# N2onboardTelemetry.net
KiCad netlist of a schematic drawn in EasyEDA
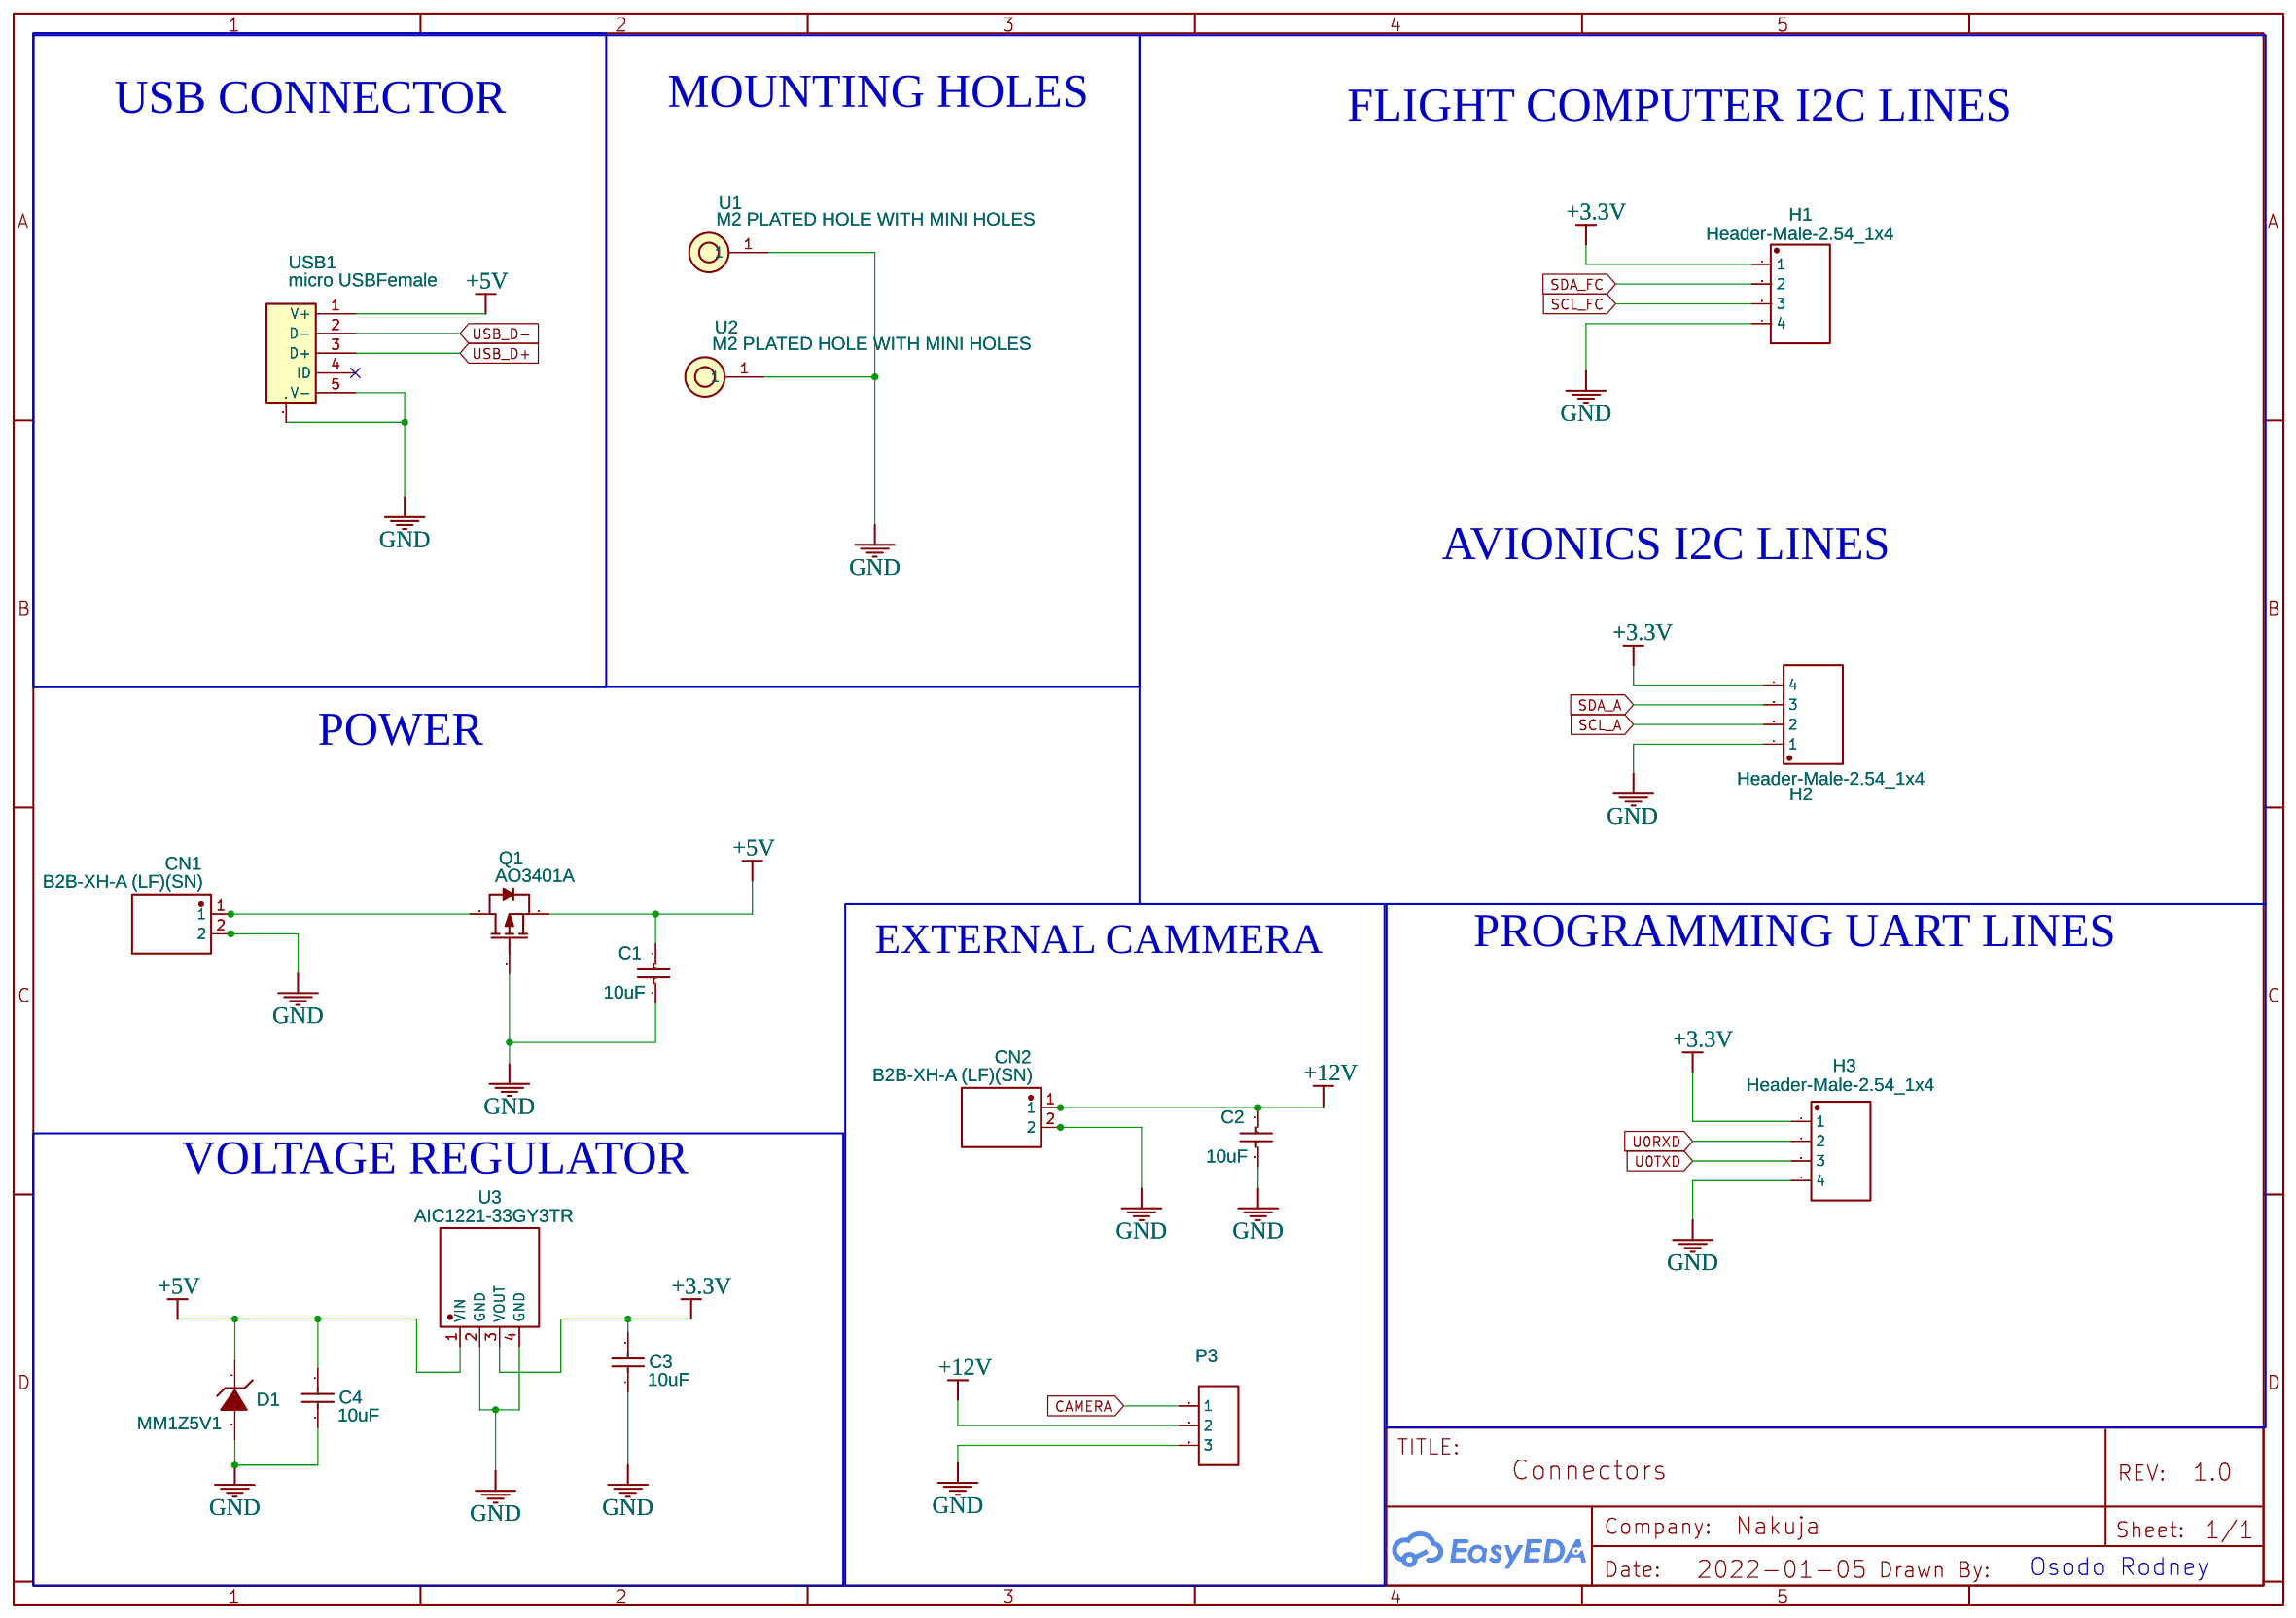
[diagram p0: Connectors]
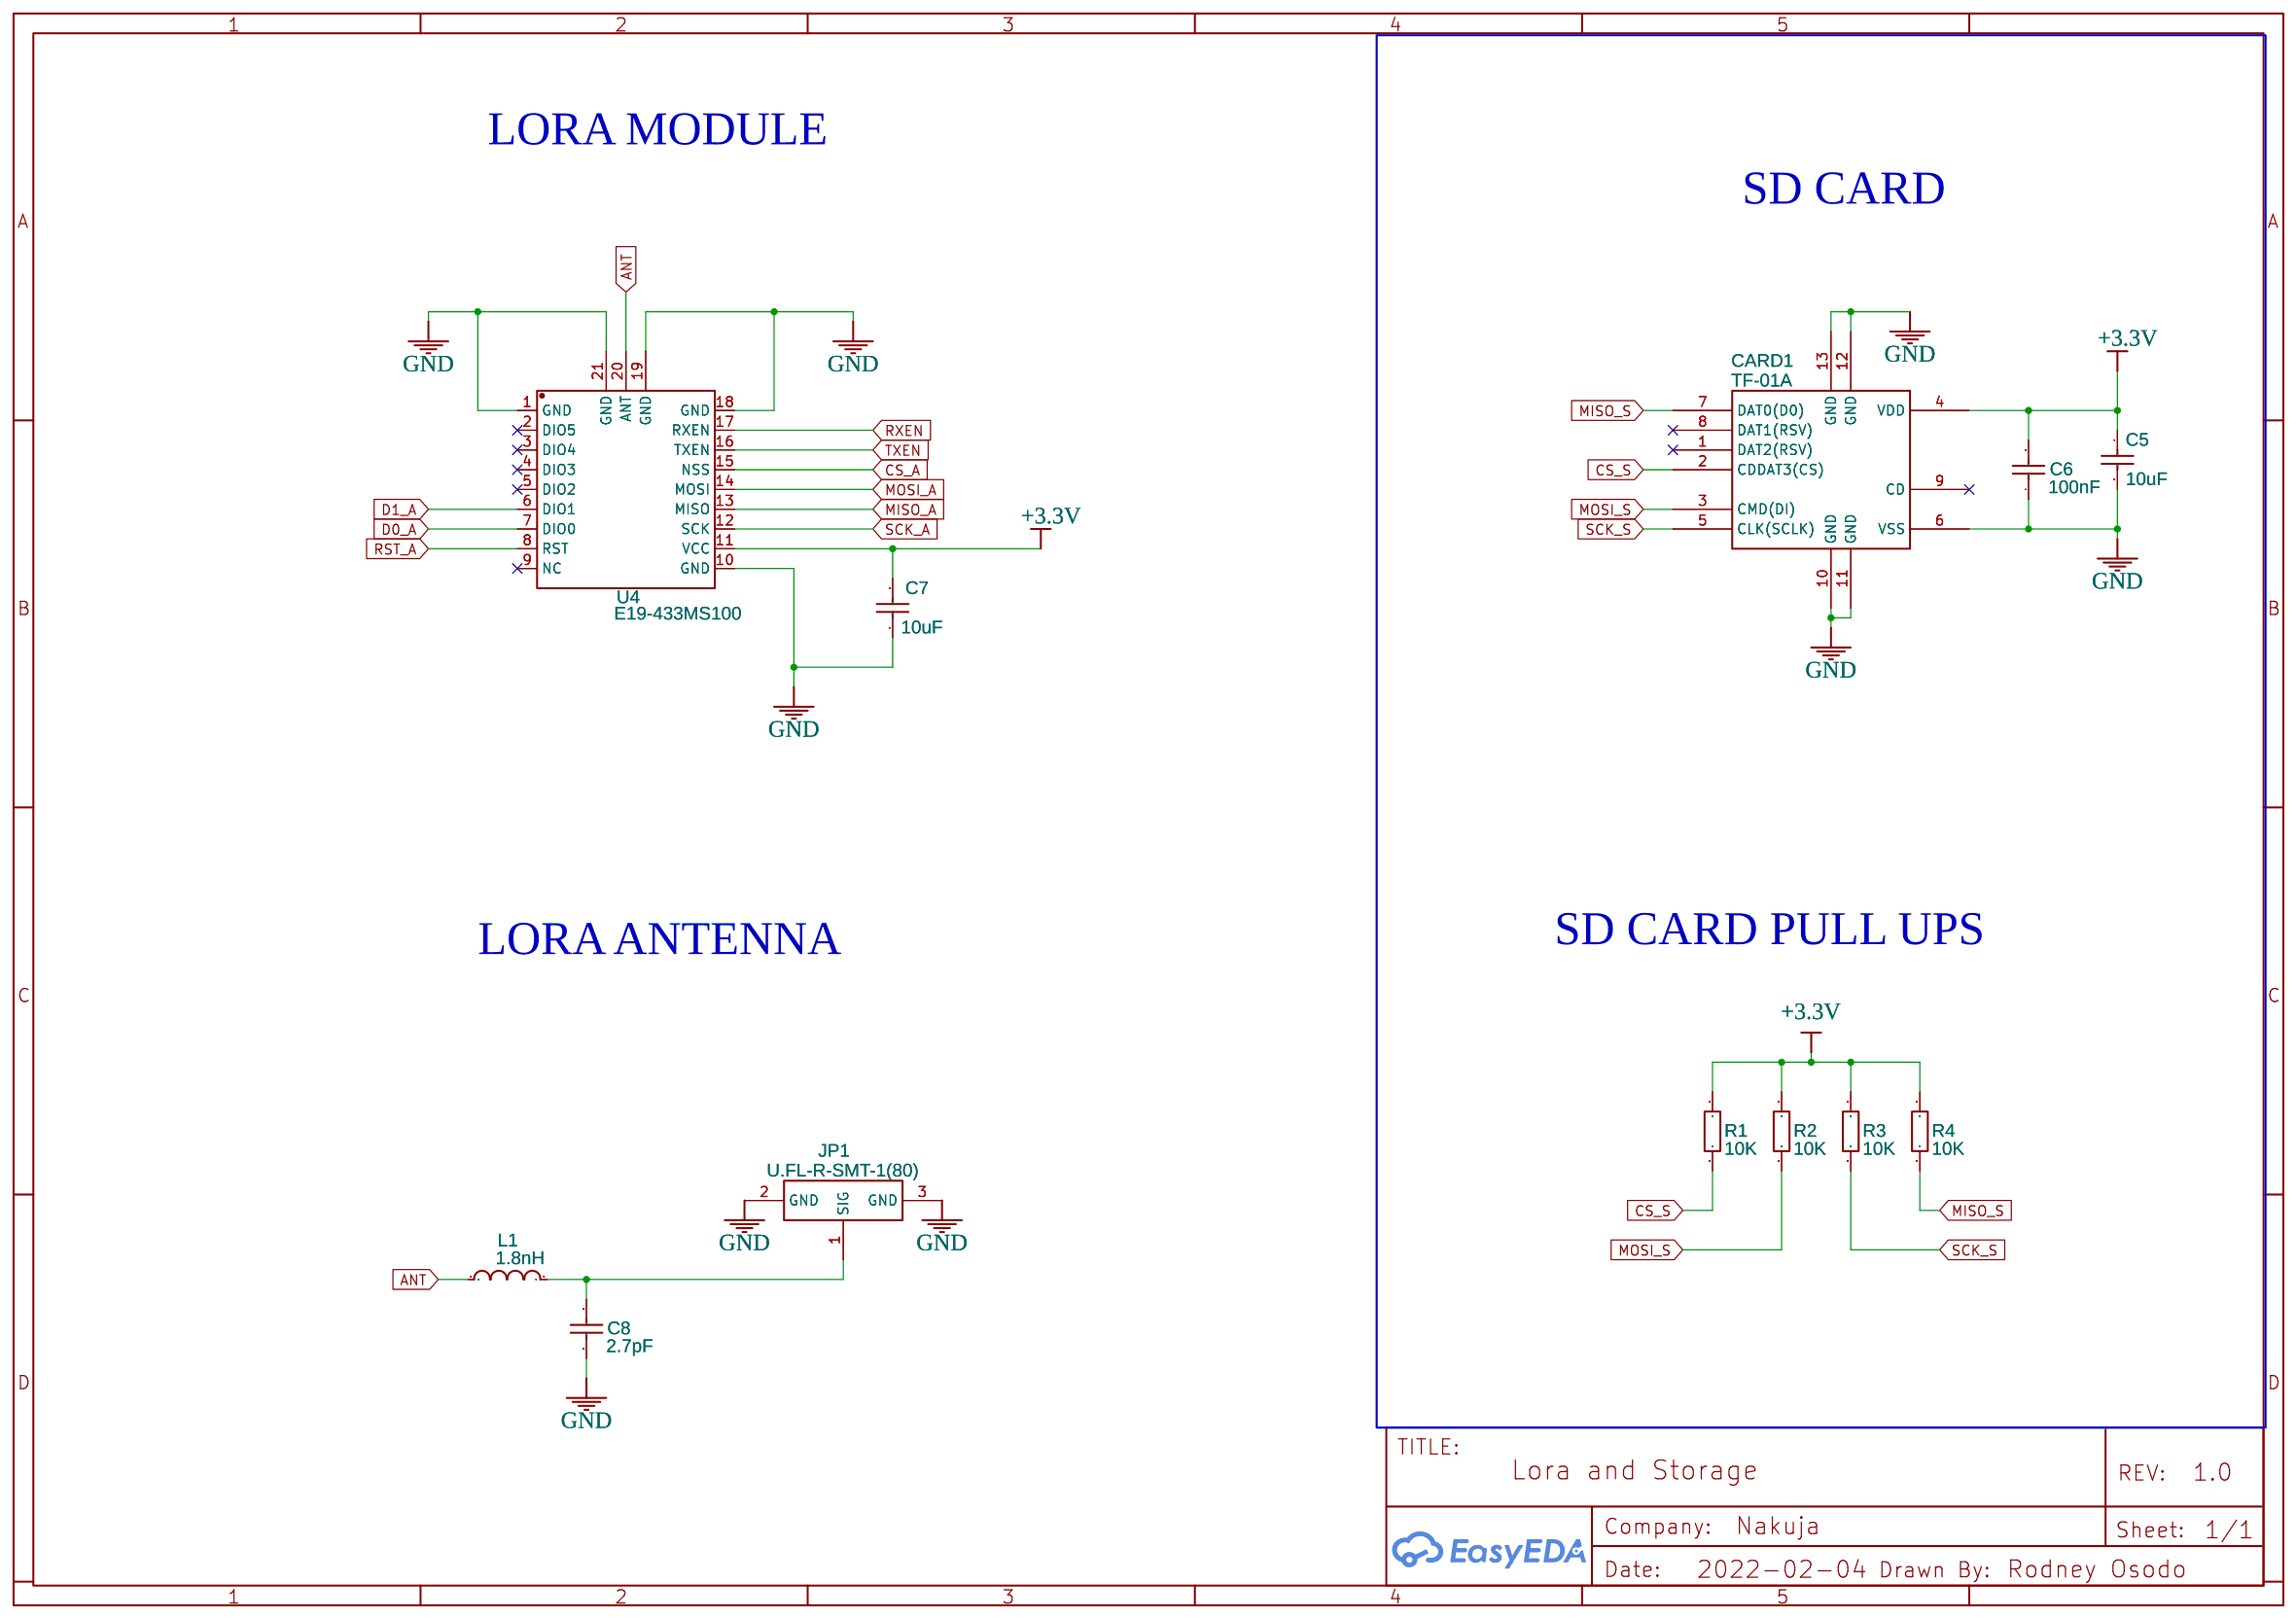
[diagram p1: lora&storage]
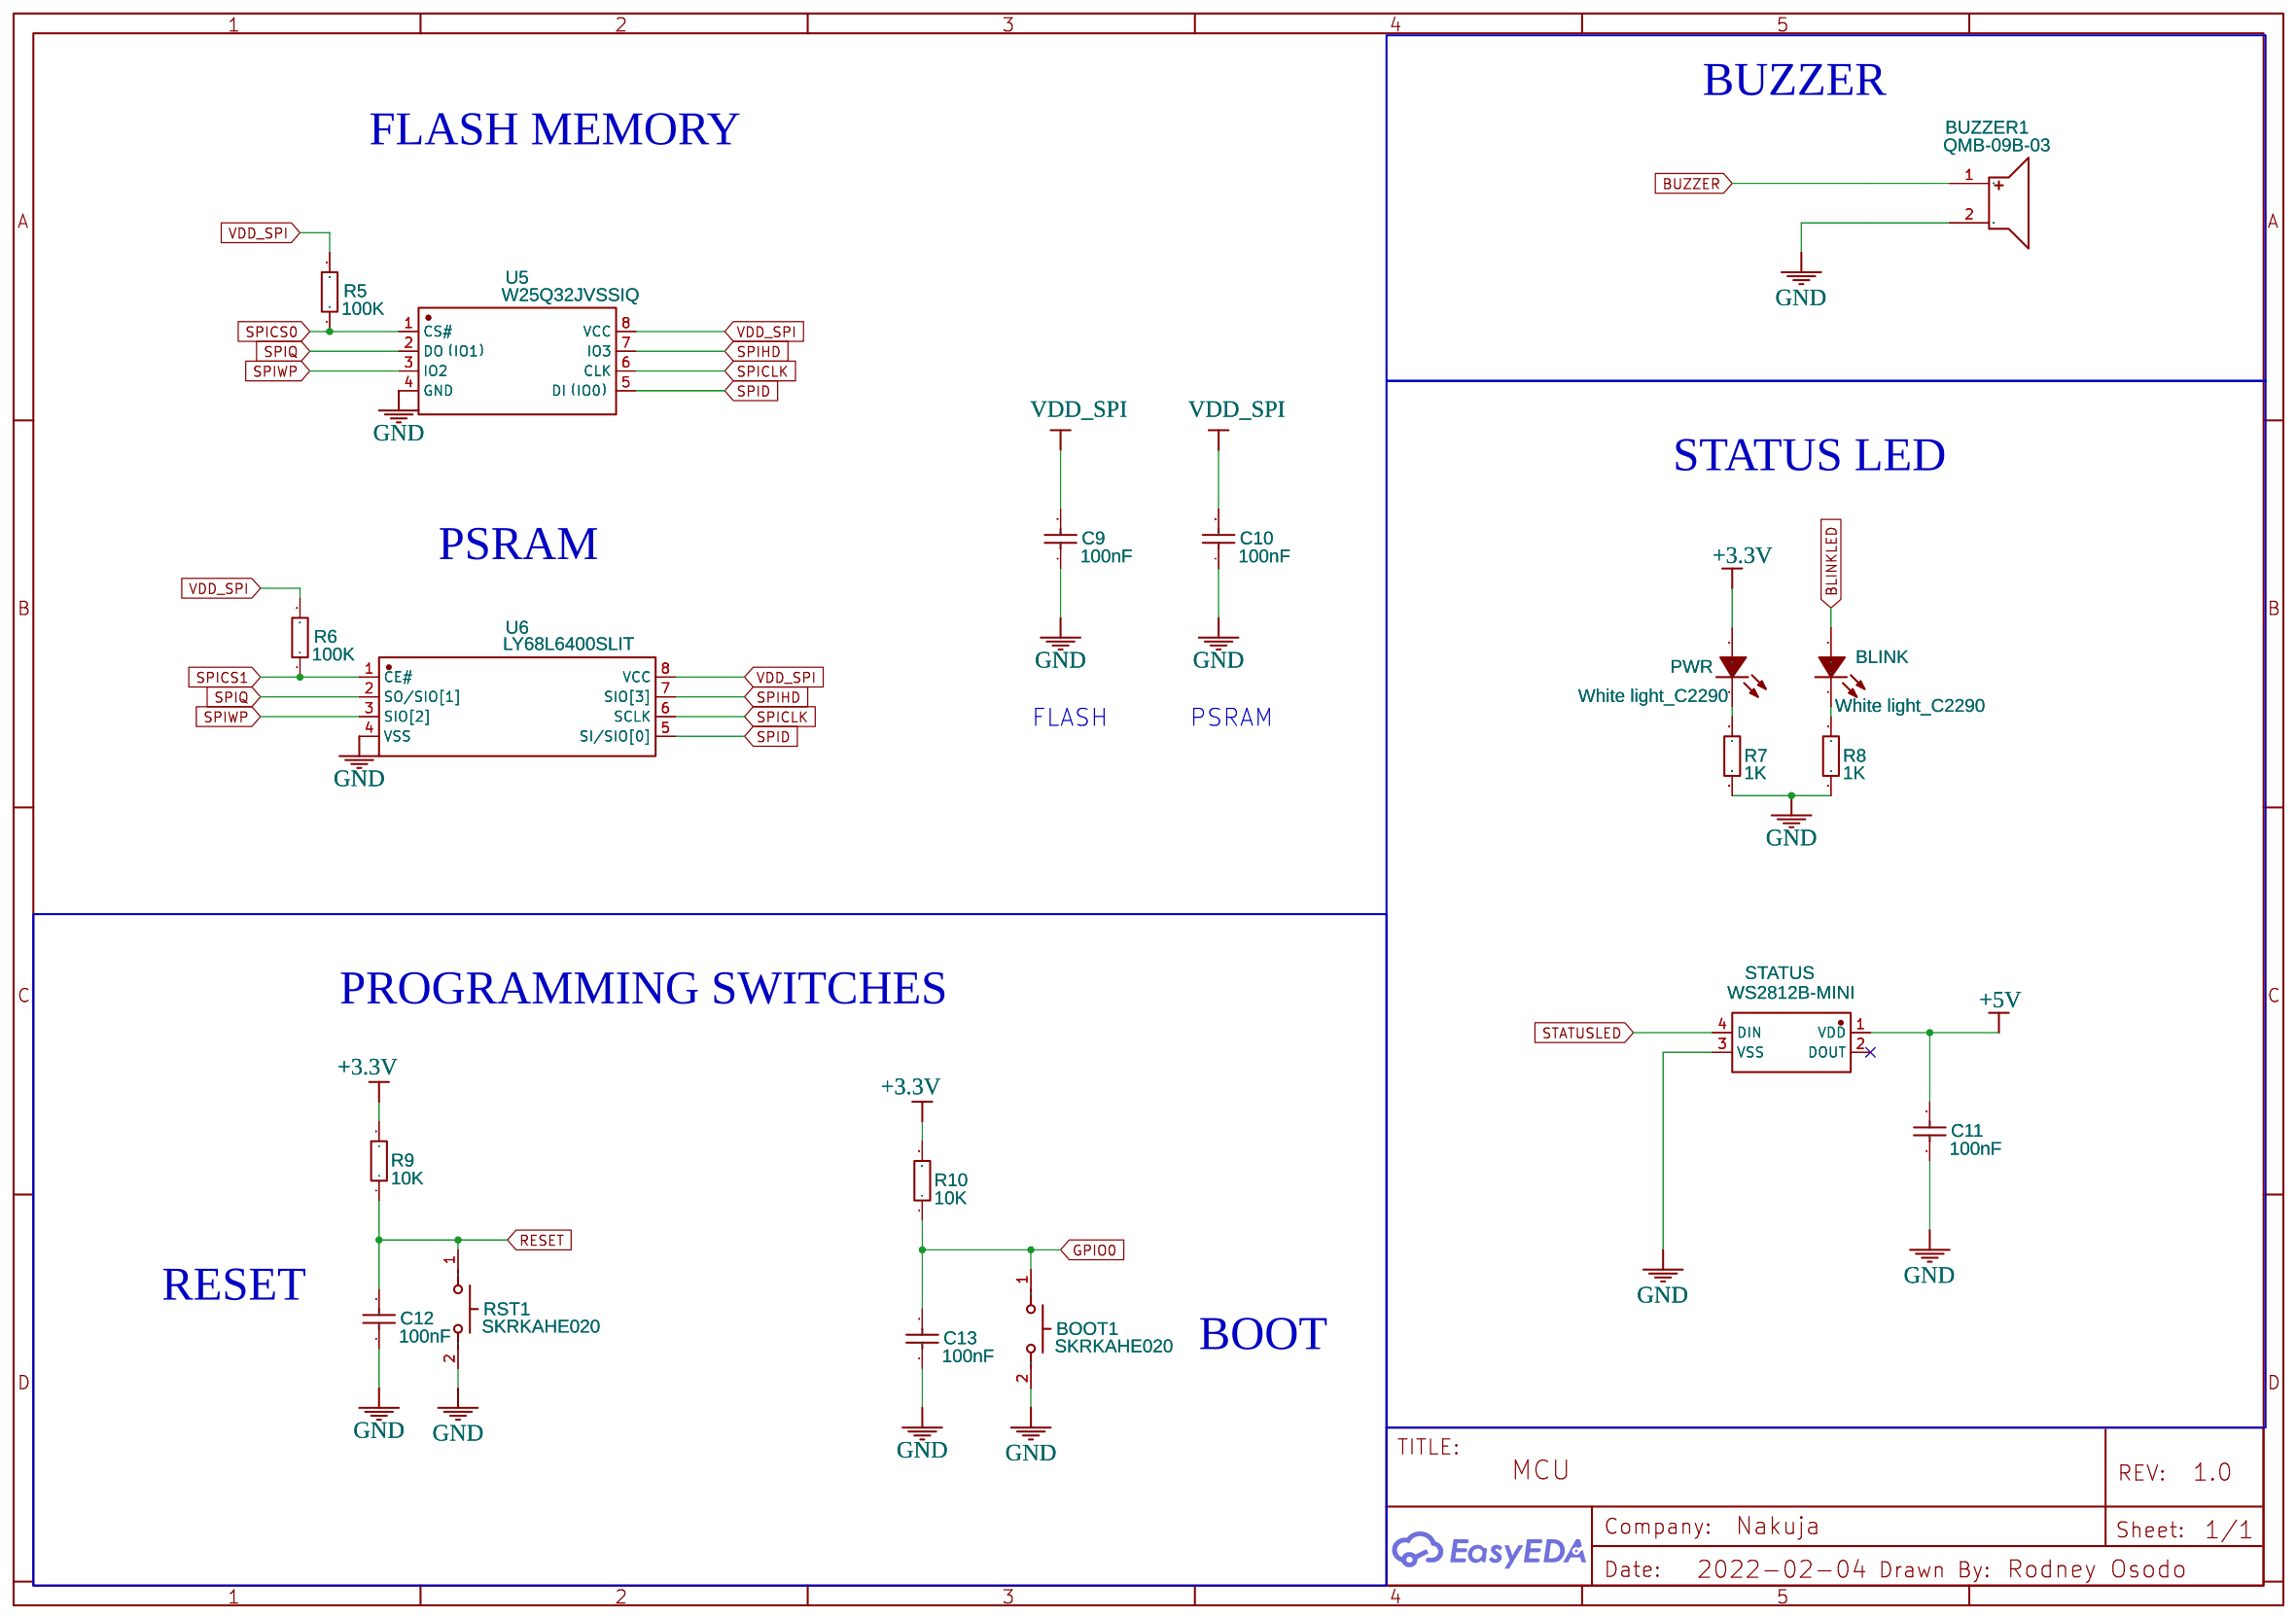
[diagram p2: Peripherals]
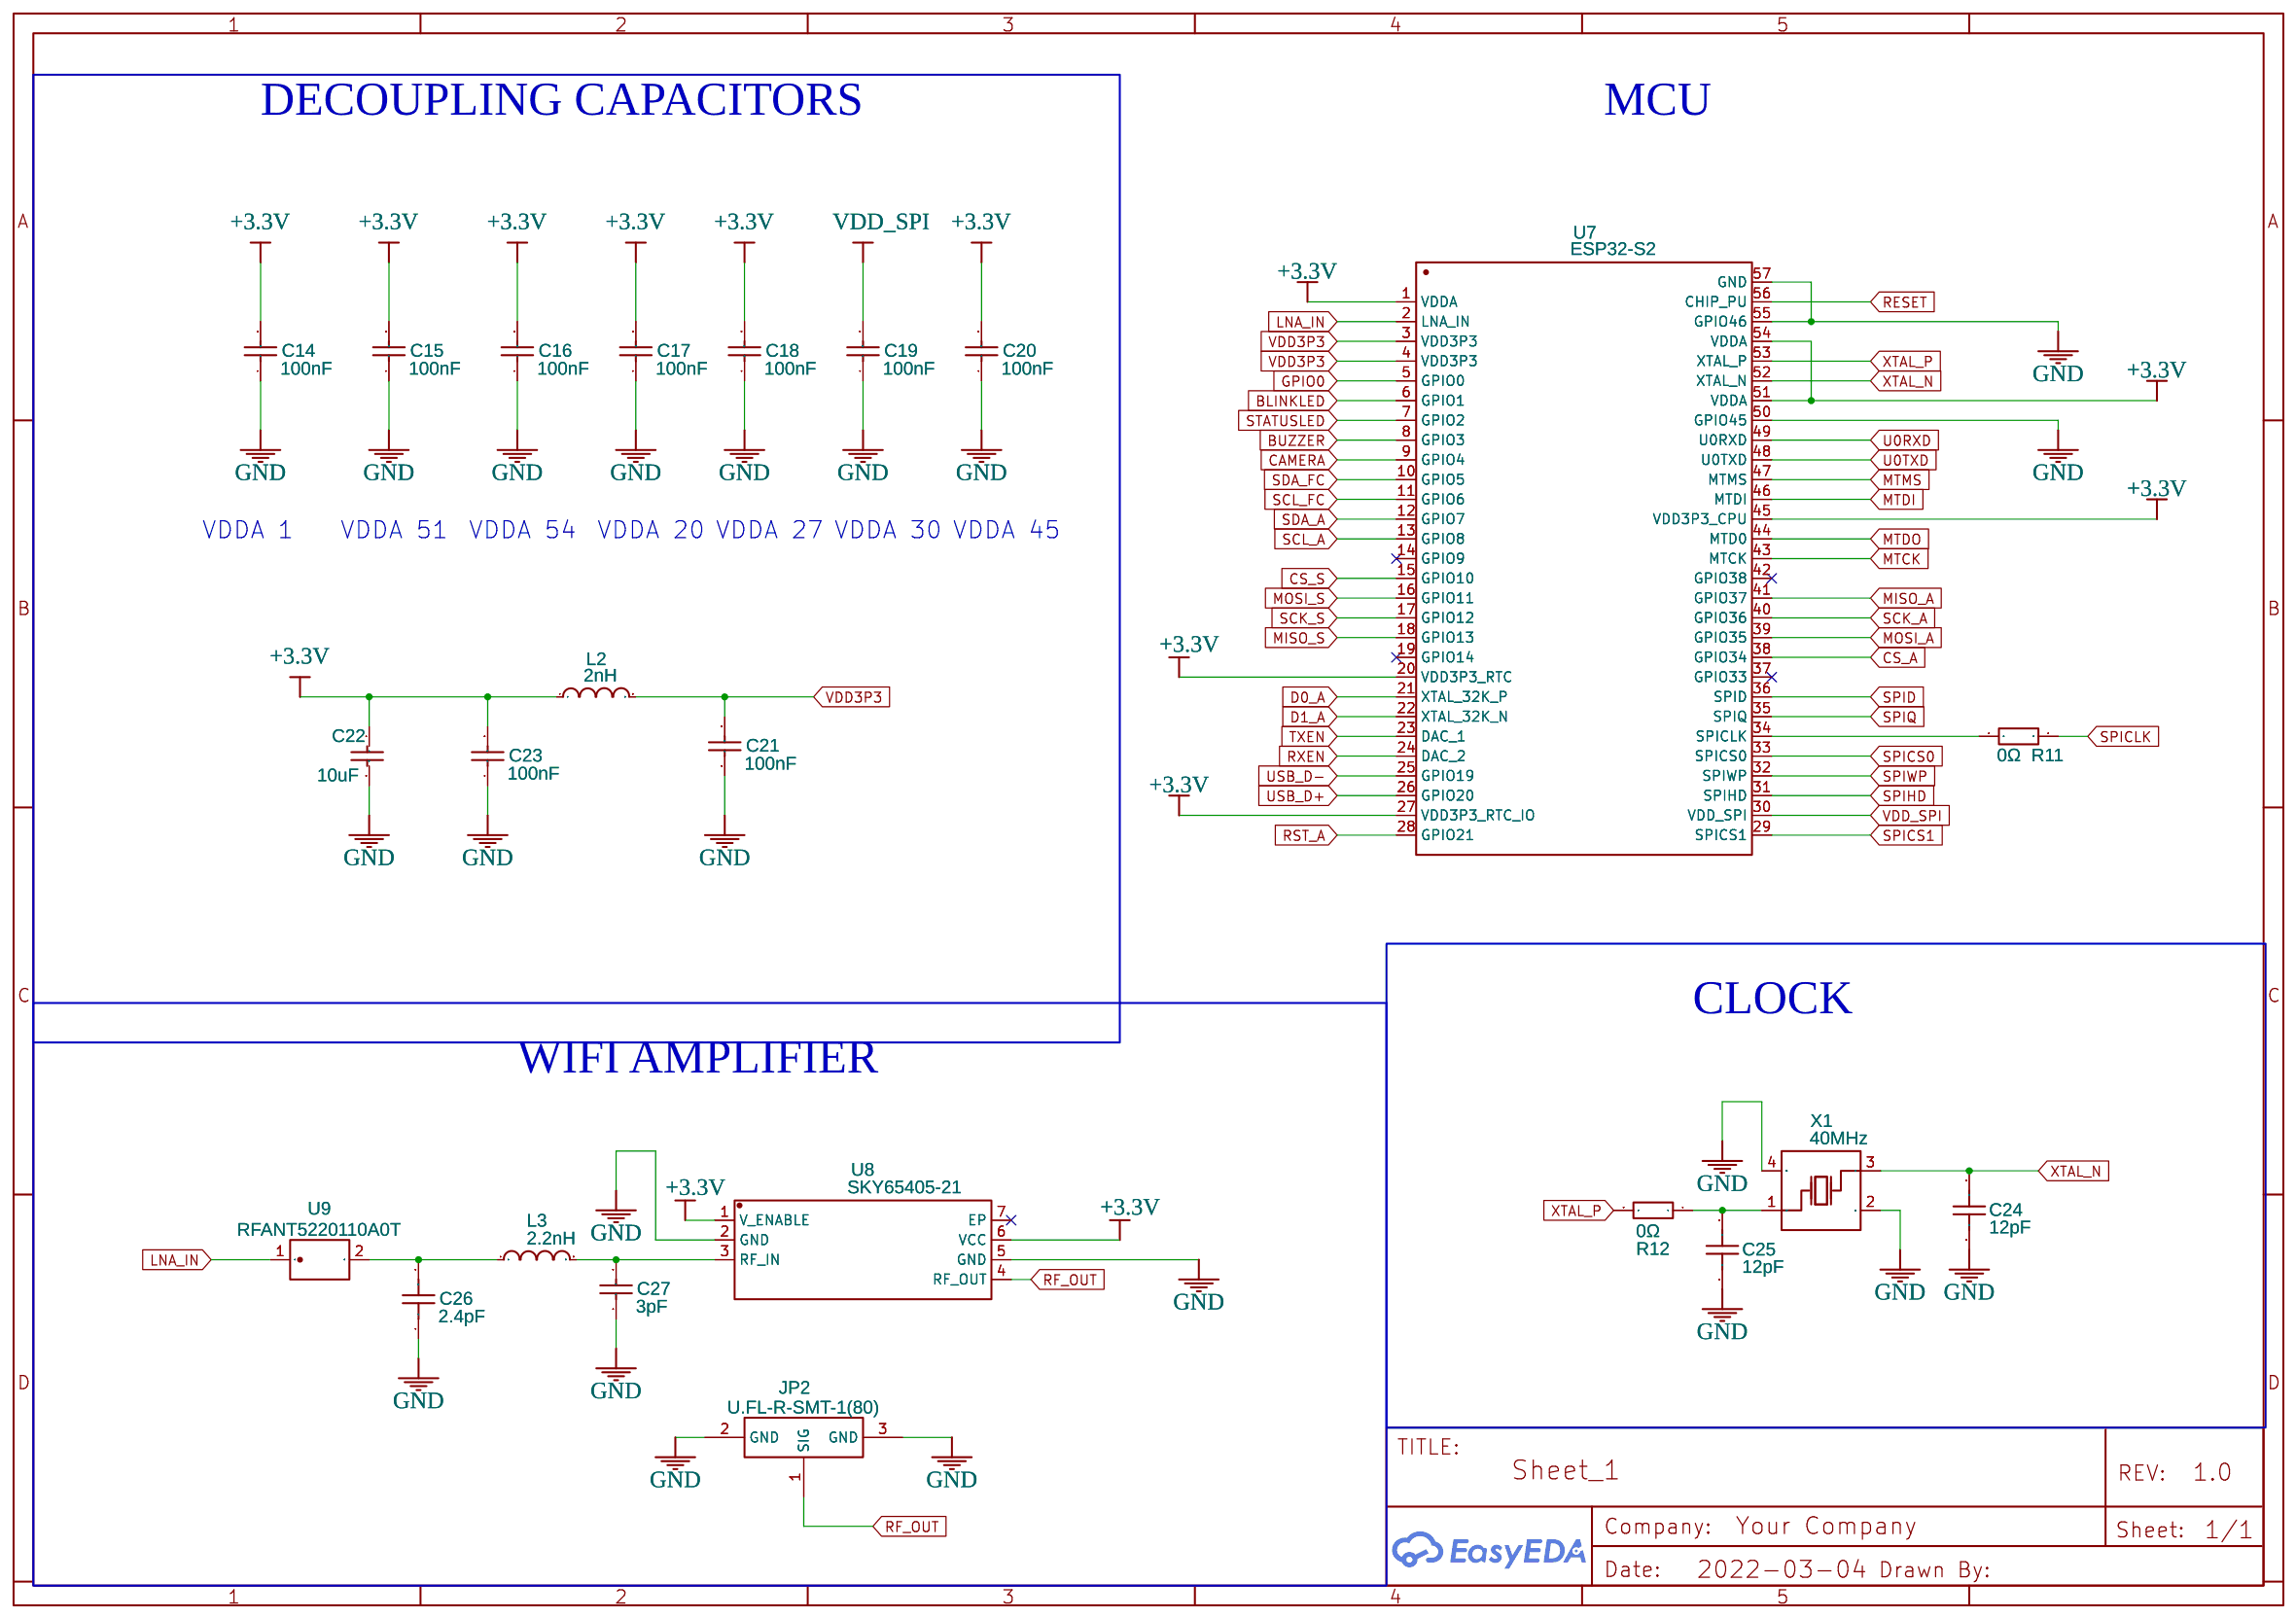
[diagram p3: MCU]
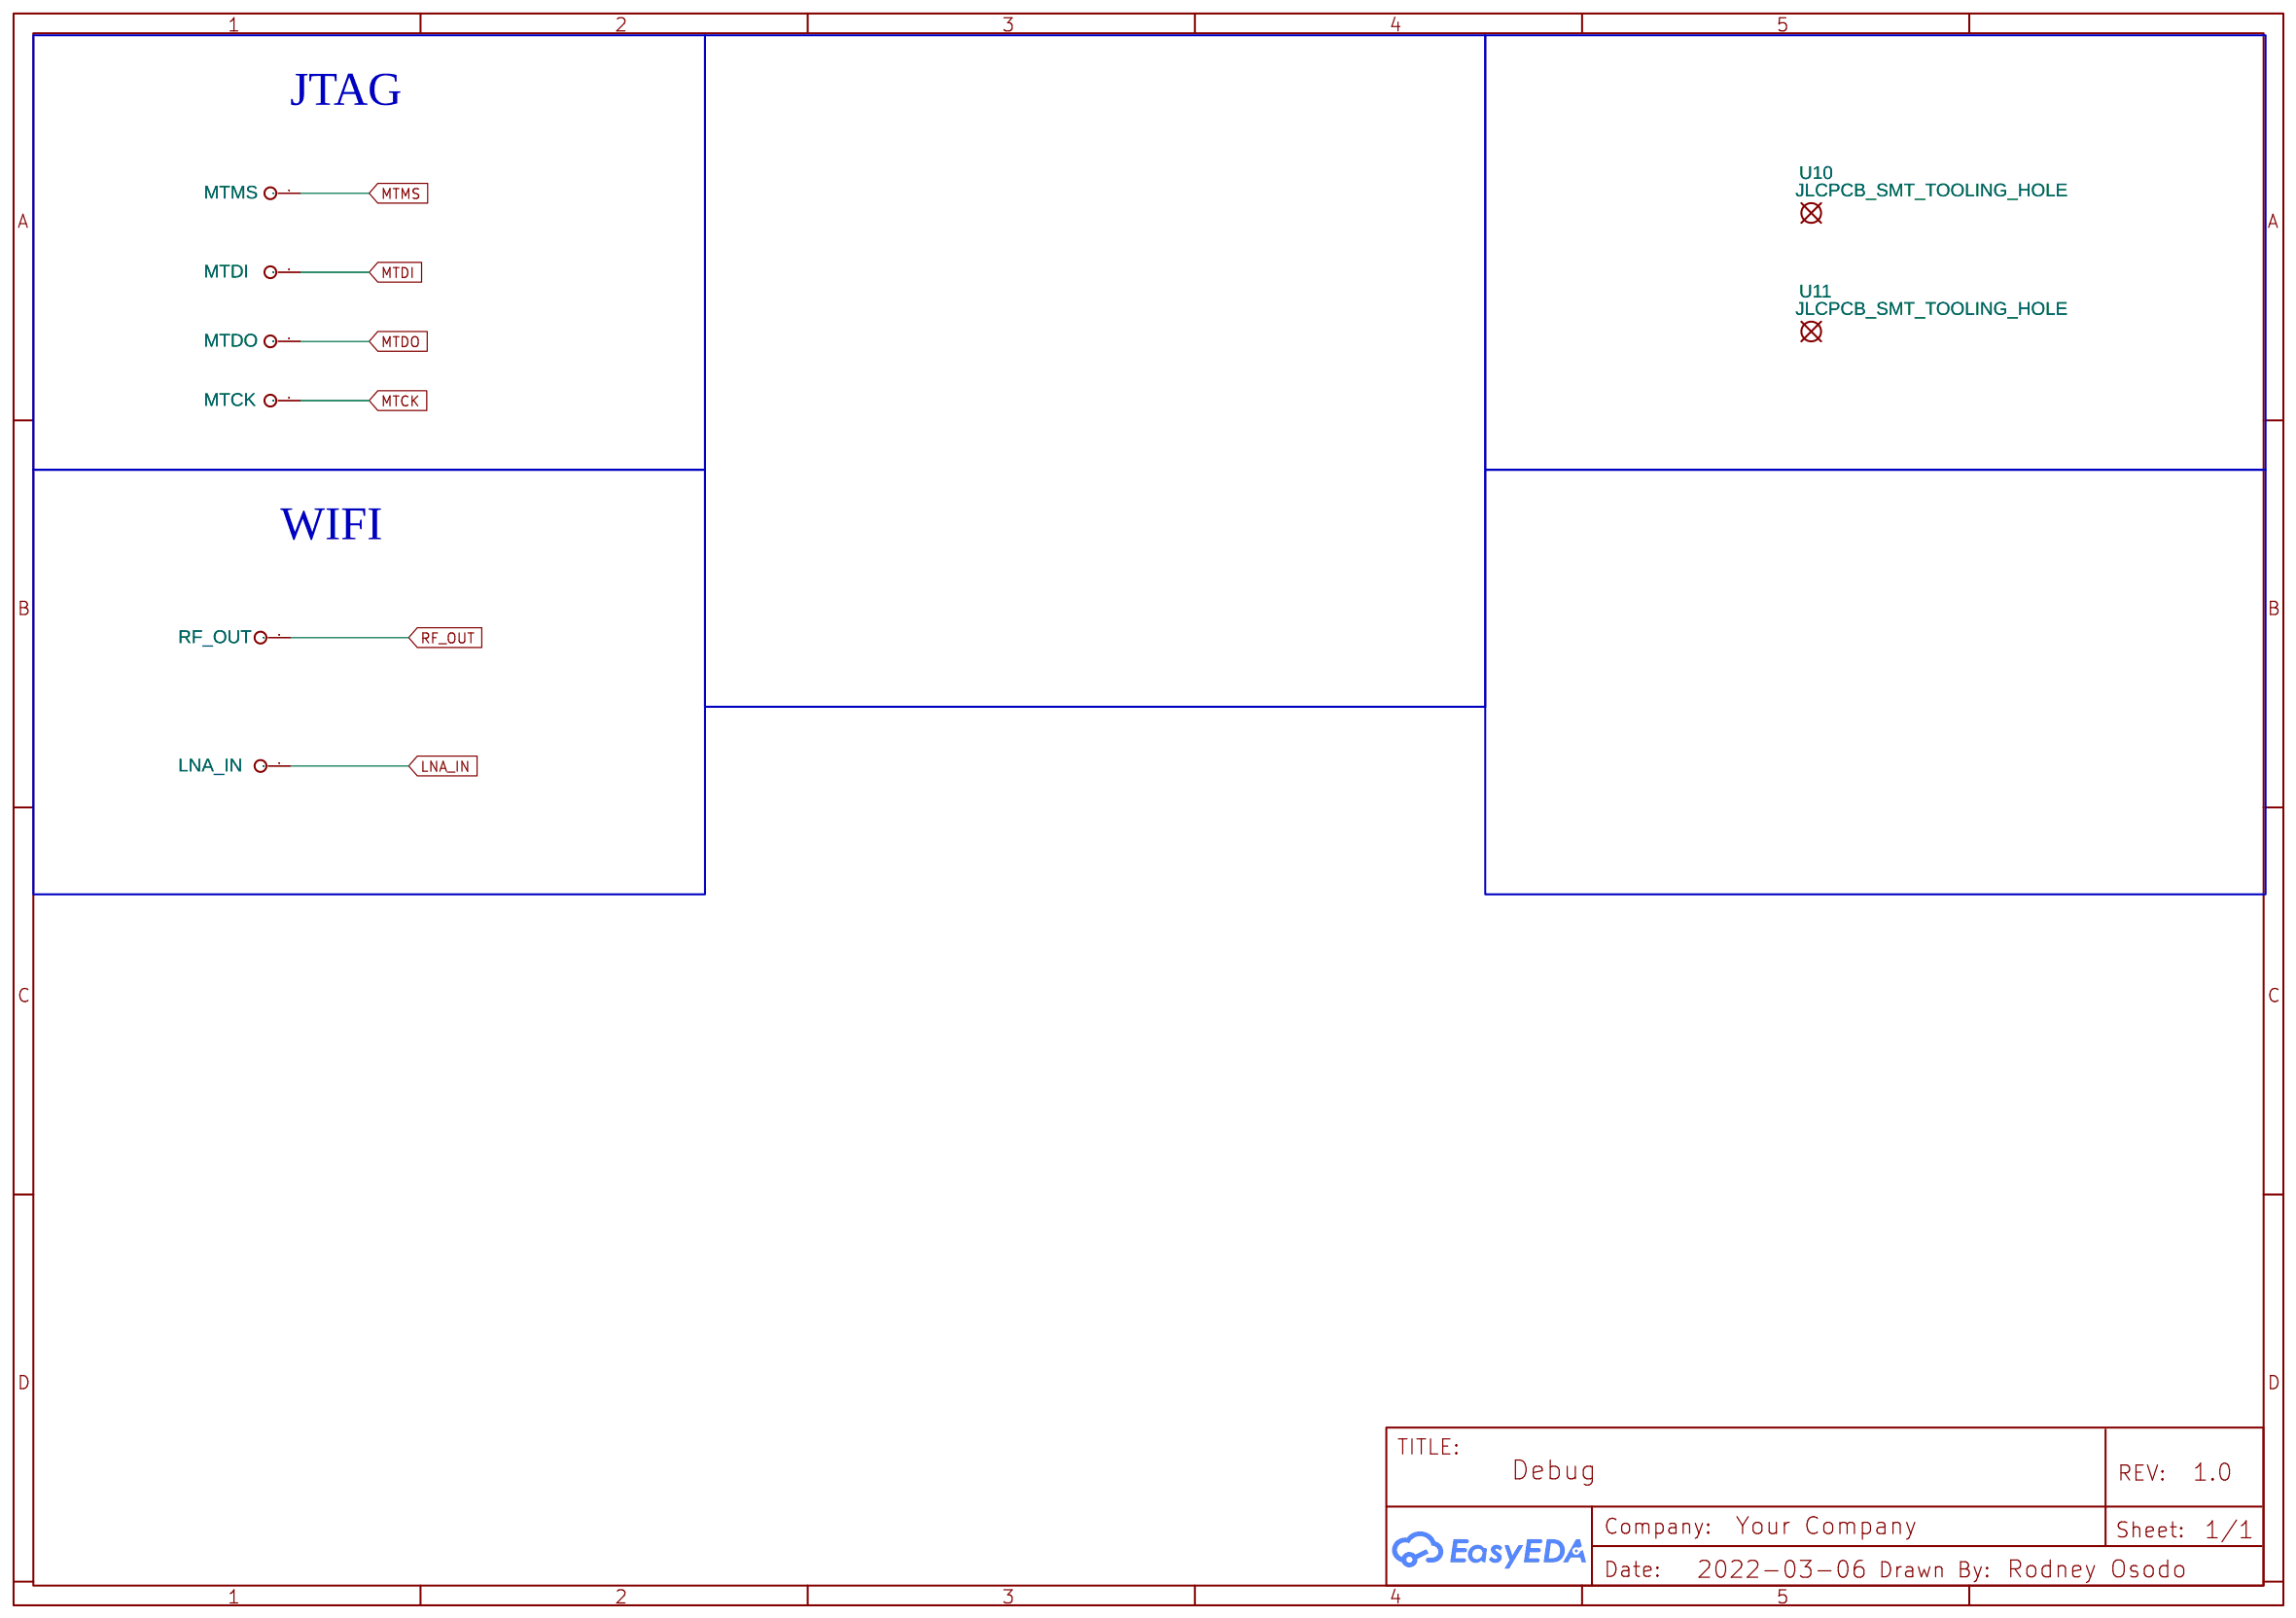
[diagram p4: Debug]

(export (version "E")
  (design (tool "Eeschema 10.0.6"))
  (components
    (comp (ref "C1")
      (value "10uF")
      (fields
        (field (name "BOM_Manufacturer Part") "CL05A106MQ5NUNC")
        (field (name "BOM_Supplier Part") "C15525")
      )
      (libsource (lib "") (part "CL05A106MQ5NUNC_1"))
    )
    (comp (ref "C2")
      (value "10uF")
      (fields
        (field (name "BOM_Manufacturer Part") "CL05A106MQ5NUNC")
        (field (name "BOM_Supplier Part") "C15525")
      )
      (libsource (lib "") (part "CL05A106MQ5NUNC_1"))
    )
    (comp (ref "C3")
      (value "10uF")
      (fields
        (field (name "BOM_Manufacturer Part") "CL05A106MQ5NUNC")
        (field (name "BOM_Supplier Part") "C15525")
      )
      (libsource (lib "") (part "CL05A106MQ5NUNC"))
    )
    (comp (ref "C4")
      (value "10uF")
      (fields
        (field (name "BOM_Manufacturer Part") "CL05A106MQ5NUNC")
        (field (name "BOM_Supplier Part") "C15525")
      )
      (libsource (lib "") (part "CL05A106MQ5NUNC"))
    )
    (comp (ref "CN1")
      (value "B2B-XH-A (LF)(SN)")
      (fields (field (name "BOM_Supplier Part") "C158012"))
      (libsource (lib "") (part "B2B-XH-A (LF)(SN)"))
    )
    (comp (ref "CN2")
      (value "B2B-XH-A (LF)(SN)")
      (fields (field (name "BOM_Supplier Part") "C158012"))
      (libsource (lib "") (part "B2B-XH-A (LF)(SN)"))
    )
    (comp (ref "D1")
      (value "MM1Z5V1")
      (fields (field (name "BOM_Supplier Part") "C81601"))
      (libsource (lib "") (part "MM1Z5V1"))
    )
    (comp (ref "H1")
      (value "Header-Male-2.54_1x4")
      (fields
        (field (name "BOM_Manufacturer Part") "210S-1*4P L=11.6MMGold-plated black")
        (field (name "BOM_Supplier Part") "C124378")
      )
      (libsource (lib "") (part "Header-Male-2.54_1x4_2"))
    )
    (comp (ref "H2")
      (value "Header-Male-2.54_1x4")
      (fields
        (field (name "BOM_Manufacturer Part") "210S-1*4P L=11.6MMGold-plated black")
        (field (name "BOM_Supplier Part") "C124378")
      )
      (libsource (lib "") (part "Header-Male-2.54_1x4_1"))
    )
    (comp (ref "H3")
      (value "Header-Male-2.54_1x4")
      (fields
        (field (name "BOM_Manufacturer Part") "210S-1*4P L=11.6MMGold-plated black")
        (field (name "BOM_Supplier Part") "C124378")
      )
      (libsource (lib "") (part "Header-Male-2.54_1x4"))
    )
    (comp (ref "P3")
      (value "HEADER-PINS_2.54_03PIN_01ROW COPY")
      (libsource (lib "") (part "HEADER-PINS_2.54_03PIN_01ROW COPY"))
    )
    (comp (ref "Q1")
      (value "AO3401A")
      (fields (field (name "BOM_Supplier Part") "C15127"))
      (libsource (lib "") (part "AO3401A"))
    )
    (comp (ref "U1")
      (value "M2 PLATED HOLE WITH MINI HOLES")
      (libsource (lib "") (part "M2 PLATED HOLE WITH MINI HOLES"))
    )
    (comp (ref "U2")
      (value "M2 PLATED HOLE WITH MINI HOLES")
      (libsource (lib "") (part "M2 PLATED HOLE WITH MINI HOLES"))
    )
    (comp (ref "U3")
      (value "AIC1221-33GY3TR")
      (fields (field (name "BOM_Supplier Part") "C211622"))
      (libsource (lib "") (part "AIC1221-33GY3TR"))
    )
    (comp (ref "USB1")
      (value "micro USBFemale")
      (fields (field (name "BOM_Supplier Part") "C10418"))
      (libsource (lib "") (part "micro USBFemale"))
    )
    (comp (ref "C5")
      (value "10uF")
      (fields
        (field (name "BOM_Manufacturer Part") "CL05A106MQ5NUNC")
        (field (name "BOM_Supplier Part") "C15525")
      )
      (libsource (lib "") (part "CL05A106MQ5NUNC"))
    )
    (comp (ref "C6")
      (value "100nF")
      (fields
        (field (name "BOM_Manufacturer Part") "CL05B104KO5NNNC")
        (field (name "BOM_Supplier Part") "C1525")
      )
      (libsource (lib "") (part "CL05B104KO5NNNC"))
    )
    (comp (ref "C7")
      (value "10uF")
      (fields
        (field (name "BOM_Manufacturer Part") "CL05A106MQ5NUNC")
        (field (name "BOM_Supplier Part") "C15525")
      )
      (libsource (lib "") (part "CL05A106MQ5NUNC"))
    )
    (comp (ref "C8")
      (value "2.7pF")
      (fields
        (field (name "BOM_Manufacturer Part") "0402CG2R7C500NT")
        (field (name "BOM_Supplier Part") "C1561")
      )
      (libsource (lib "") (part "0402CG2R7C500NT"))
    )
    (comp (ref "CARD1")
      (value "TF-01A")
      (fields (field (name "BOM_Supplier Part") "C91145"))
      (libsource (lib "") (part "TF-01A"))
    )
    (comp (ref "JP1")
      (value "U.FL-R-SMT-1(80)")
      (fields (field (name "BOM_Supplier Part") "C88374"))
      (libsource (lib "") (part "U.FL-R-SMT-1(80)"))
    )
    (comp (ref "L1")
      (value "1.8nH")
      (fields
        (field (name "BOM_Manufacturer Part") "HK10051N8S-T")
        (field (name "BOM_Supplier Part") "C89157")
      )
      (libsource (lib "") (part "HK10051N8S-T"))
    )
    (comp (ref "R1")
      (value "10K")
      (fields
        (field (name "BOM_Manufacturer Part") "RTT02103JTH")
        (field (name "BOM_Supplier Part") "C102759")
      )
      (libsource (lib "") (part "RTT02103JTH"))
    )
    (comp (ref "R2")
      (value "10K")
      (fields
        (field (name "BOM_Manufacturer Part") "RTT02103JTH")
        (field (name "BOM_Supplier Part") "C102759")
      )
      (libsource (lib "") (part "RTT02103JTH"))
    )
    (comp (ref "R3")
      (value "10K")
      (fields
        (field (name "BOM_Manufacturer Part") "RTT02103JTH")
        (field (name "BOM_Supplier Part") "C102759")
      )
      (libsource (lib "") (part "RTT02103JTH"))
    )
    (comp (ref "R4")
      (value "10K")
      (fields
        (field (name "BOM_Manufacturer Part") "RTT02103JTH")
        (field (name "BOM_Supplier Part") "C102759")
      )
      (libsource (lib "") (part "RTT02103JTH"))
    )
    (comp (ref "U4")
      (value "E19-433MS100")
      (fields (field (name "BOM_Supplier Part") "C97346"))
      (libsource (lib "") (part "E19-433MS100"))
    )
    (comp (ref "BLINK")
      (value "White light_C2290")
      (fields
        (field (name "BOM_Manufacturer Part") "0603White light")
        (field (name "BOM_Supplier Part") "C2290")
      )
      (libsource (lib "") (part "0603White light_C2290_1"))
    )
    (comp (ref "BOOT1")
      (value "SKRKAHE020")
      (fields (field (name "BOM_Supplier Part") "C202388"))
      (libsource (lib "") (part "SKRKAHE020"))
    )
    (comp (ref "BUZZER1")
      (value "QMB-09B-03")
      (fields (field (name "BOM_Supplier Part") "C96256"))
      (libsource (lib "") (part "QMB-09B-03"))
    )
    (comp (ref "C9")
      (value "100nF")
      (fields
        (field (name "BOM_Manufacturer Part") "CL05B104KO5NNNC")
        (field (name "BOM_Supplier Part") "C1525")
      )
      (libsource (lib "") (part "CL05B104KO5NNNC"))
    )
    (comp (ref "C10")
      (value "100nF")
      (fields
        (field (name "BOM_Manufacturer Part") "CL05B104KO5NNNC")
        (field (name "BOM_Supplier Part") "C1525")
      )
      (libsource (lib "") (part "CL05B104KO5NNNC"))
    )
    (comp (ref "C11")
      (value "100nF")
      (fields
        (field (name "BOM_Manufacturer Part") "CL05B104KO5NNNC")
        (field (name "BOM_Supplier Part") "C1525")
      )
      (libsource (lib "") (part "CL05B104KO5NNNC"))
    )
    (comp (ref "C12")
      (value "100nF")
      (fields
        (field (name "BOM_Manufacturer Part") "CL05B104KO5NNNC")
        (field (name "BOM_Supplier Part") "C1525")
      )
      (libsource (lib "") (part "CL05B104KO5NNNC"))
    )
    (comp (ref "C13")
      (value "100nF")
      (fields
        (field (name "BOM_Manufacturer Part") "CL05B104KO5NNNC")
        (field (name "BOM_Supplier Part") "C1525")
      )
      (libsource (lib "") (part "CL05B104KO5NNNC"))
    )
    (comp (ref "PWR")
      (value "White light_C2290")
      (fields
        (field (name "BOM_Manufacturer Part") "0603White light")
        (field (name "BOM_Supplier Part") "C2290")
      )
      (libsource (lib "") (part "0603White light_C2290"))
    )
    (comp (ref "R5")
      (value "100K")
      (fields
        (field (name "BOM_Manufacturer Part") "0402WGF1003TCE")
        (field (name "BOM_Supplier Part") "C25741")
      )
      (libsource (lib "") (part "0402WGF1003TCE"))
    )
    (comp (ref "R6")
      (value "100K")
      (fields
        (field (name "BOM_Manufacturer Part") "0402WGF1003TCE")
        (field (name "BOM_Supplier Part") "C25741")
      )
      (libsource (lib "") (part "0402WGF1003TCE"))
    )
    (comp (ref "R7")
      (value "1K")
      (fields
        (field (name "BOM_Manufacturer Part") "0402WGF5101TCE")
        (field (name "BOM_Supplier Part") "C25905")
      )
      (libsource (lib "") (part "0402WGF5101TCE"))
    )
    (comp (ref "R8")
      (value "1K")
      (fields
        (field (name "BOM_Manufacturer Part") "0402WGF5101TCE")
        (field (name "BOM_Supplier Part") "C25905")
      )
      (libsource (lib "") (part "0402WGF5101TCE_1"))
    )
    (comp (ref "R9")
      (value "10K")
      (fields
        (field (name "BOM_Manufacturer Part") "RTT02103JTH")
        (field (name "BOM_Supplier Part") "C102759")
      )
      (libsource (lib "") (part "RTT02103JTH"))
    )
    (comp (ref "R10")
      (value "10K")
      (fields
        (field (name "BOM_Manufacturer Part") "RTT02103JTH")
        (field (name "BOM_Supplier Part") "C102759")
      )
      (libsource (lib "") (part "RTT02103JTH"))
    )
    (comp (ref "RST1")
      (value "SKRKAHE020")
      (fields (field (name "BOM_Supplier Part") "C202388"))
      (libsource (lib "") (part "SKRKAHE020_1"))
    )
    (comp (ref "STATUS")
      (value "WS2812B-MINI")
      (fields
        (field (name "BOM_Manufacturer Part") "WS2812B-Mini")
        (field (name "BOM_Supplier Part") "C527089")
      )
      (libsource (lib "") (part "WS2812B-MINI"))
    )
    (comp (ref "U5")
      (value "W25Q32JVSSIQ")
      (fields (field (name "BOM_Supplier Part") "C82344"))
      (libsource (lib "") (part "W25Q32JVSSIQ"))
    )
    (comp (ref "U6")
      (value "LY68L6400SLIT")
      (fields (field (name "BOM_Supplier Part") "C261881"))
      (libsource (lib "") (part "LY68L6400SLIT"))
    )
    (comp (ref "C14")
      (value "100nF")
      (fields
        (field (name "BOM_Manufacturer Part") "CL05B104KO5NNNC")
        (field (name "BOM_Supplier Part") "C1525")
      )
      (libsource (lib "") (part "CL05B104KO5NNNC"))
    )
    (comp (ref "C15")
      (value "100nF")
      (fields
        (field (name "BOM_Manufacturer Part") "CL05B104KO5NNNC")
        (field (name "BOM_Supplier Part") "C1525")
      )
      (libsource (lib "") (part "CL05B104KO5NNNC"))
    )
    (comp (ref "C16")
      (value "100nF")
      (fields
        (field (name "BOM_Manufacturer Part") "CL05B104KO5NNNC")
        (field (name "BOM_Supplier Part") "C1525")
      )
      (libsource (lib "") (part "CL05B104KO5NNNC"))
    )
    (comp (ref "C17")
      (value "100nF")
      (fields
        (field (name "BOM_Manufacturer Part") "CL05B104KO5NNNC")
        (field (name "BOM_Supplier Part") "C1525")
      )
      (libsource (lib "") (part "CL05B104KO5NNNC"))
    )
    (comp (ref "C18")
      (value "100nF")
      (fields
        (field (name "BOM_Manufacturer Part") "CL05B104KO5NNNC")
        (field (name "BOM_Supplier Part") "C1525")
      )
      (libsource (lib "") (part "CL05B104KO5NNNC"))
    )
    (comp (ref "C19")
      (value "100nF")
      (fields
        (field (name "BOM_Manufacturer Part") "CL05B104KO5NNNC")
        (field (name "BOM_Supplier Part") "C1525")
      )
      (libsource (lib "") (part "CL05B104KO5NNNC"))
    )
    (comp (ref "C20")
      (value "100nF")
      (fields
        (field (name "BOM_Manufacturer Part") "CL05B104KO5NNNC")
        (field (name "BOM_Supplier Part") "C1525")
      )
      (libsource (lib "") (part "CL05B104KO5NNNC"))
    )
    (comp (ref "C21")
      (value "100nF")
      (fields
        (field (name "BOM_Manufacturer Part") "CL05B104KO5NNNC")
        (field (name "BOM_Supplier Part") "C1525")
      )
      (libsource (lib "") (part "CL05B104KO5NNNC"))
    )
    (comp (ref "C22")
      (value "10uF")
      (fields
        (field (name "BOM_Manufacturer Part") "CL05A106MQ5NUNC")
        (field (name "BOM_Supplier Part") "C15525")
      )
      (libsource (lib "") (part "CL05A106MQ5NUNC"))
    )
    (comp (ref "C23")
      (value "100nF")
      (fields
        (field (name "BOM_Manufacturer Part") "CL05B104KO5NNNC")
        (field (name "BOM_Supplier Part") "C1525")
      )
      (libsource (lib "") (part "CL05B104KO5NNNC"))
    )
    (comp (ref "C24")
      (value "12pF")
      (fields
        (field (name "BOM_Manufacturer Part") "0402N120F500CT")
        (field (name "BOM_Supplier Part") "C555399")
      )
      (libsource (lib "") (part "0402N120F500CT"))
    )
    (comp (ref "C25")
      (value "12pF")
      (fields
        (field (name "BOM_Manufacturer Part") "0402N120F500CT")
        (field (name "BOM_Supplier Part") "C555399")
      )
      (libsource (lib "") (part "0402N120F500CT"))
    )
    (comp (ref "C26")
      (value "2.4pF")
      (fields
        (field (name "BOM_Manufacturer Part") "0402N2R4B500")
        (field (name "BOM_Supplier Part") "C123475")
      )
      (libsource (lib "") (part "0402N2R4B500"))
    )
    (comp (ref "C27")
      (value "3pF")
      (fields
        (field (name "BOM_Manufacturer Part") "CL05C030BB5NNNC")
        (field (name "BOM_Supplier Part") "C318583")
      )
      (libsource (lib "") (part "CL05C030BB5NNNC"))
    )
    (comp (ref "JP2")
      (value "U.FL-R-SMT-1(80)")
      (fields (field (name "BOM_Supplier Part") "C88374"))
      (libsource (lib "") (part "U.FL-R-SMT-1(80)"))
    )
    (comp (ref "L2")
      (value "2nH")
      (fields
        (field (name "BOM_Manufacturer Part") "MLG1005S2N0BT000")
        (field (name "BOM_Supplier Part") "C76769")
      )
      (libsource (lib "") (part "MLG1005S2N0BT000"))
    )
    (comp (ref "L3")
      (value "2.2nH")
      (fields
        (field (name "BOM_Manufacturer Part") "SDCL1005C2N2STDF")
        (field (name "BOM_Supplier Part") "C27122")
      )
      (libsource (lib "") (part "SDCL1005C2N2STDF"))
    )
    (comp (ref "R11")
      (value "0Ω")
      (fields
        (field (name "BOM_Manufacturer Part") "RC-02000FT")
        (field (name "BOM_Supplier Part") "C140225")
      )
      (libsource (lib "") (part "RC-02000FT"))
    )
    (comp (ref "R12")
      (value "0Ω")
      (fields
        (field (name "BOM_Manufacturer Part") "RC-02000FT")
        (field (name "BOM_Supplier Part") "C140225")
      )
      (libsource (lib "") (part "RC-02000FT"))
    )
    (comp (ref "U7")
      (value "ESP32-S2")
      (fields (field (name "BOM_Supplier Part") "C529594"))
      (libsource (lib "") (part "ESP32-S2"))
    )
    (comp (ref "U8")
      (value "SKY65405-21")
      (fields (field (name "BOM_Supplier Part") "C80314"))
      (libsource (lib "") (part "SKY65405-21"))
    )
    (comp (ref "U9")
      (value "RFANT5220110A0T")
      (fields (field (name "BOM_Supplier Part") "C127611"))
      (libsource (lib "") (part "RFANT5220110A0T"))
    )
    (comp (ref "X1")
      (value "40MHz")
      (fields
        (field (name "BOM_Manufacturer Part") "S3240000121040")
        (field (name "BOM_Supplier Part") "C426989")
      )
      (libsource (lib "") (part "S3240000121040"))
    )
    (comp (ref "LNA_IN") (value "TESTPOINT_1MM") (libsource (lib "") (part "TESTPOINT_1MM_2")))
    (comp (ref "MTCK") (value "TESTPOINT_1MM") (libsource (lib "") (part "TESTPOINT_1MM_1")))
    (comp (ref "MTDI") (value "TESTPOINT_1MM") (libsource (lib "") (part "TESTPOINT_1MM")))
    (comp (ref "MTDO") (value "TESTPOINT_1MM") (libsource (lib "") (part "TESTPOINT_1MM_4")))
    (comp (ref "MTMS") (value "TESTPOINT_1MM") (libsource (lib "") (part "TESTPOINT_1MM_5")))
    (comp (ref "RF_OUT") (value "TESTPOINT_1MM") (libsource (lib "") (part "TESTPOINT_1MM_3")))
    (comp (ref "U10") (value "JLCPCB_SMT_TOOLING_HOLE") (libsource (lib "") (part "JLCPCB_SMT_TOOLING_HOLE")))
    (comp (ref "U11") (value "JLCPCB_SMT_TOOLING_HOLE") (libsource (lib "") (part "JLCPCB_SMT_TOOLING_HOLE")))
  )
  (nets
    (net (code "1") (name "+3.3V") (class "Default")
      (node (ref "C14") (pin "2") (pinfunction "2_2") (pintype "input"))
      (node (ref "C15") (pin "2") (pinfunction "2_2") (pintype "input"))
      (node (ref "C16") (pin "2") (pinfunction "2_2") (pintype "input"))
      (node (ref "C17") (pin "2") (pinfunction "2_2") (pintype "input"))
      (node (ref "C18") (pin "2") (pinfunction "2_2") (pintype "input"))
      (node (ref "C20") (pin "2") (pinfunction "2_2") (pintype "input"))
      (node (ref "C22") (pin "1") (pinfunction "1_1") (pintype "input"))
      (node (ref "C23") (pin "2") (pinfunction "2_2") (pintype "input"))
      (node (ref "C3") (pin "2") (pinfunction "2_2") (pintype "input"))
      (node (ref "C5") (pin "1") (pinfunction "1_1") (pintype "input"))
      (node (ref "C6") (pin "2") (pinfunction "2_2") (pintype "input"))
      (node (ref "C7") (pin "1") (pinfunction "1_1") (pintype "input"))
      (node (ref "CARD1") (pin "4") (pinfunction "VDD_4") (pintype "input"))
      (node (ref "H1") (pin "1") (pinfunction "1_1") (pintype "unspecified"))
      (node (ref "H2") (pin "4") (pinfunction "4_4") (pintype "unspecified"))
      (node (ref "H3") (pin "1") (pinfunction "1_1") (pintype "unspecified"))
      (node (ref "L2") (pin "1") (pinfunction "1_1") (pintype "unspecified"))
      (node (ref "PWR") (pin "1") (pinfunction "A_1") (pintype "unspecified"))
      (node (ref "R1") (pin "2") (pinfunction "2_2") (pintype "input"))
      (node (ref "R10") (pin "2") (pinfunction "2_2") (pintype "input"))
      (node (ref "R2") (pin "2") (pinfunction "2_2") (pintype "input"))
      (node (ref "R3") (pin "2") (pinfunction "2_2") (pintype "input"))
      (node (ref "R4") (pin "2") (pinfunction "2_2") (pintype "input"))
      (node (ref "R9") (pin "2") (pinfunction "2_2") (pintype "input"))
      (node (ref "U3") (pin "3") (pinfunction "VOUT_3") (pintype "unspecified"))
      (node (ref "U4") (pin "11") (pinfunction "VCC_11") (pintype "unspecified"))
      (node (ref "U7") (pin "1") (pinfunction "VDDA_1") (pintype "unspecified"))
      (node (ref "U7") (pin "20") (pinfunction "VDD3P3_RTC_20") (pintype "unspecified"))
      (node (ref "U7") (pin "27") (pinfunction "VDD3P3_RTC_IO_27") (pintype "unspecified"))
      (node (ref "U7") (pin "45") (pinfunction "VDD3P3_CPU_45") (pintype "unspecified"))
      (node (ref "U7") (pin "51") (pinfunction "VDDA_51") (pintype "unspecified"))
      (node (ref "U7") (pin "54") (pinfunction "VDDA_54") (pintype "unspecified"))
      (node (ref "U8") (pin "1") (pinfunction "V_ENABLE_1") (pintype "unspecified"))
      (node (ref "U8") (pin "6") (pinfunction "VCC_6") (pintype "unspecified"))
    )
    (net (code "2") (name "+5V") (class "Default")
      (node (ref "C1") (pin "1") (pinfunction "1_1") (pintype "input"))
      (node (ref "C11") (pin "2") (pinfunction "2_2") (pintype "input"))
      (node (ref "C4") (pin "2") (pinfunction "2_2") (pintype "input"))
      (node (ref "D1") (pin "1") (pinfunction "C_1") (pintype "unspecified"))
      (node (ref "Q1") (pin "2") (pinfunction "S_2") (pintype "unspecified"))
      (node (ref "STATUS") (pin "1") (pinfunction "VDD_1") (pintype "unspecified"))
      (node (ref "U3") (pin "1") (pinfunction "VIN_1") (pintype "unspecified"))
      (node (ref "USB1") (pin "1") (pinfunction "V+_1") (pintype "unspecified"))
    )
    (net (code "3") (name "+12V") (class "Default")
      (node (ref "C2") (pin "1") (pinfunction "1_1") (pintype "input"))
      (node (ref "CN2") (pin "1") (pinfunction "1_1") (pintype "unspecified"))
      (node (ref "P3") (pin "2") (pinfunction "2_2") (pintype "unspecified"))
    )
    (net (code "4") (name "ANT") (class "Default")
      (node (ref "L1") (pin "1") (pinfunction "1_1") (pintype "unspecified"))
      (node (ref "U4") (pin "20") (pinfunction "ANT_20") (pintype "unspecified"))
    )
    (net (code "5") (name "BLINKLED") (class "Default")
      (node (ref "BLINK") (pin "1") (pinfunction "A_1") (pintype "unspecified"))
      (node (ref "U7") (pin "6") (pinfunction "GPIO1_6") (pintype "unspecified"))
    )
    (net (code "6") (name "BUZZER") (class "Default")
      (node (ref "BUZZER1") (pin "1") (pinfunction "1_1") (pintype "unspecified"))
      (node (ref "U7") (pin "8") (pinfunction "GPIO3_8") (pintype "unspecified"))
    )
    (net (code "7") (name "CAMERA") (class "Default")
      (node (ref "P3") (pin "1") (pinfunction "1_1") (pintype "unspecified"))
      (node (ref "U7") (pin "9") (pinfunction "GPIO4_9") (pintype "unspecified"))
    )
    (net (code "8") (name "CS_A") (class "Default")
      (node (ref "U4") (pin "15") (pinfunction "NSS_15") (pintype "unspecified"))
      (node (ref "U7") (pin "38") (pinfunction "GPIO34_38") (pintype "unspecified"))
    )
    (net (code "9") (name "CS_S") (class "Default")
      (node (ref "CARD1") (pin "2") (pinfunction "CDDAT3(CS)_2") (pintype "bidirectional"))
      (node (ref "R1") (pin "1") (pinfunction "1_1") (pintype "input"))
      (node (ref "U7") (pin "15") (pinfunction "GPIO10_15") (pintype "unspecified"))
    )
    (net (code "10") (name "D0_A") (class "Default")
      (node (ref "U4") (pin "7") (pinfunction "DIO0_7") (pintype "unspecified"))
      (node (ref "U7") (pin "21") (pinfunction "XTAL_32K_P_21") (pintype "unspecified"))
    )
    (net (code "11") (name "D1_A") (class "Default")
      (node (ref "U4") (pin "6") (pinfunction "DIO1_6") (pintype "unspecified"))
      (node (ref "U7") (pin "22") (pinfunction "XTAL_32K_N_22") (pintype "unspecified"))
    )
    (net (code "12") (name "GND") (class "Default")
      (node (ref "BOOT1") (pin "2") (pinfunction "2_2") (pintype "unspecified"))
      (node (ref "BUZZER1") (pin "2") (pinfunction "2_2") (pintype "unspecified"))
      (node (ref "C1") (pin "2") (pinfunction "2_2") (pintype "input"))
      (node (ref "C10") (pin "1") (pinfunction "1_1") (pintype "input"))
      (node (ref "C11") (pin "1") (pinfunction "1_1") (pintype "input"))
      (node (ref "C12") (pin "1") (pinfunction "1_1") (pintype "input"))
      (node (ref "C13") (pin "1") (pinfunction "1_1") (pintype "input"))
      (node (ref "C14") (pin "1") (pinfunction "1_1") (pintype "input"))
      (node (ref "C15") (pin "1") (pinfunction "1_1") (pintype "input"))
      (node (ref "C16") (pin "1") (pinfunction "1_1") (pintype "input"))
      (node (ref "C17") (pin "1") (pinfunction "1_1") (pintype "input"))
      (node (ref "C18") (pin "1") (pinfunction "1_1") (pintype "input"))
      (node (ref "C19") (pin "1") (pinfunction "1_1") (pintype "input"))
      (node (ref "C2") (pin "2") (pinfunction "2_2") (pintype "input"))
      (node (ref "C20") (pin "1") (pinfunction "1_1") (pintype "input"))
      (node (ref "C21") (pin "1") (pinfunction "1_1") (pintype "input"))
      (node (ref "C22") (pin "2") (pinfunction "2_2") (pintype "input"))
      (node (ref "C23") (pin "1") (pinfunction "1_1") (pintype "input"))
      (node (ref "C24") (pin "1") (pinfunction "1_1") (pintype "unspecified"))
      (node (ref "C25") (pin "1") (pinfunction "1_1") (pintype "unspecified"))
      (node (ref "C26") (pin "1") (pinfunction "1_1") (pintype "unspecified"))
      (node (ref "C27") (pin "1") (pinfunction "1_1") (pintype "input"))
      (node (ref "C3") (pin "1") (pinfunction "1_1") (pintype "input"))
      (node (ref "C4") (pin "1") (pinfunction "1_1") (pintype "input"))
      (node (ref "C5") (pin "2") (pinfunction "2_2") (pintype "input"))
      (node (ref "C6") (pin "1") (pinfunction "1_1") (pintype "input"))
      (node (ref "C7") (pin "2") (pinfunction "2_2") (pintype "input"))
      (node (ref "C8") (pin "1") (pinfunction "1_1") (pintype "input"))
      (node (ref "C9") (pin "1") (pinfunction "1_1") (pintype "input"))
      (node (ref "CARD1") (pin "10") (pinfunction "GND_10") (pintype "input"))
      (node (ref "CARD1") (pin "11") (pinfunction "GND_11") (pintype "input"))
      (node (ref "CARD1") (pin "12") (pinfunction "GND_12") (pintype "input"))
      (node (ref "CARD1") (pin "13") (pinfunction "GND_13") (pintype "input"))
      (node (ref "CARD1") (pin "6") (pinfunction "VSS_6") (pintype "input"))
      (node (ref "CN1") (pin "2") (pinfunction "2_2") (pintype "unspecified"))
      (node (ref "CN2") (pin "2") (pinfunction "2_2") (pintype "unspecified"))
      (node (ref "D1") (pin "2") (pinfunction "A_2") (pintype "unspecified"))
      (node (ref "H1") (pin "4") (pinfunction "4_4") (pintype "unspecified"))
      (node (ref "H2") (pin "1") (pinfunction "1_1") (pintype "unspecified"))
      (node (ref "H3") (pin "4") (pinfunction "4_4") (pintype "unspecified"))
      (node (ref "JP1") (pin "2") (pinfunction "GND_2") (pintype "unspecified"))
      (node (ref "JP1") (pin "3") (pinfunction "GND_3") (pintype "unspecified"))
      (node (ref "JP2") (pin "2") (pinfunction "GND_2") (pintype "unspecified"))
      (node (ref "JP2") (pin "3") (pinfunction "GND_3") (pintype "unspecified"))
      (node (ref "P3") (pin "3") (pinfunction "3_3") (pintype "unspecified"))
      (node (ref "Q1") (pin "1") (pinfunction "G_1") (pintype "unspecified"))
      (node (ref "R7") (pin "2") (pinfunction "2_2") (pintype "input"))
      (node (ref "R8") (pin "1") (pinfunction "1_1") (pintype "input"))
      (node (ref "RST1") (pin "2") (pinfunction "2_2") (pintype "unspecified"))
      (node (ref "STATUS") (pin "3") (pinfunction "VSS_3") (pintype "unspecified"))
      (node (ref "U1") (pin "1") (pinfunction "1_1") (pintype "unspecified"))
      (node (ref "U2") (pin "1") (pinfunction "1_1") (pintype "unspecified"))
      (node (ref "U3") (pin "2") (pinfunction "GND_2") (pintype "unspecified"))
      (node (ref "U3") (pin "4") (pinfunction "GND_4") (pintype "unspecified"))
      (node (ref "U4") (pin "1") (pinfunction "GND_1") (pintype "unspecified"))
      (node (ref "U4") (pin "10") (pinfunction "GND_10") (pintype "unspecified"))
      (node (ref "U4") (pin "18") (pinfunction "GND_18") (pintype "unspecified"))
      (node (ref "U4") (pin "19") (pinfunction "GND_19") (pintype "unspecified"))
      (node (ref "U4") (pin "21") (pinfunction "GND_21") (pintype "unspecified"))
      (node (ref "U5") (pin "4") (pinfunction "GND_4") (pintype "unspecified"))
      (node (ref "U6") (pin "4") (pinfunction "VSS_4") (pintype "unspecified"))
      (node (ref "U7") (pin "50") (pinfunction "GPIO45_50") (pintype "unspecified"))
      (node (ref "U7") (pin "55") (pinfunction "GPIO46_55") (pintype "unspecified"))
      (node (ref "U7") (pin "57") (pinfunction "GND_57") (pintype "unspecified"))
      (node (ref "U8") (pin "2") (pinfunction "GND_2") (pintype "unspecified"))
      (node (ref "U8") (pin "5") (pinfunction "GND_5") (pintype "unspecified"))
      (node (ref "USB1") (pin "0") (pinfunction "MTN_0") (pintype "input"))
      (node (ref "USB1") (pin "5") (pinfunction "V-_5") (pintype "unspecified"))
      (node (ref "X1") (pin "2") (pinfunction "GND_2") (pintype "unspecified"))
      (node (ref "X1") (pin "4") (pinfunction "GND_4") (pintype "unspecified"))
    )
    (net (code "13") (name "GPIO0") (class "Default")
      (node (ref "BOOT1") (pin "1") (pinfunction "1_1") (pintype "unspecified"))
      (node (ref "C13") (pin "2") (pinfunction "2_2") (pintype "input"))
      (node (ref "R10") (pin "1") (pinfunction "1_1") (pintype "input"))
      (node (ref "U7") (pin "5") (pinfunction "GPIO0_5") (pintype "unspecified"))
    )
    (net (code "14") (name "LNA_IN") (class "Default")
      (node (ref "LNA_IN") (pin "1") (pinfunction "1_1") (pintype "unspecified"))
      (node (ref "U7") (pin "2") (pinfunction "LNA_IN_2") (pintype "unspecified"))
      (node (ref "U9") (pin "1") (pinfunction "1_1") (pintype "unspecified"))
    )
    (net (code "15") (name "MISO_A") (class "Default")
      (node (ref "U4") (pin "13") (pinfunction "MISO_13") (pintype "unspecified"))
      (node (ref "U7") (pin "41") (pinfunction "GPIO37_41") (pintype "unspecified"))
    )
    (net (code "16") (name "MISO_S") (class "Default")
      (node (ref "CARD1") (pin "7") (pinfunction "DAT0(D0)_7") (pintype "bidirectional"))
      (node (ref "R4") (pin "1") (pinfunction "1_1") (pintype "input"))
      (node (ref "U7") (pin "18") (pinfunction "GPIO13_18") (pintype "unspecified"))
    )
    (net (code "17") (name "MOSI_A") (class "Default")
      (node (ref "U4") (pin "14") (pinfunction "MOSI_14") (pintype "unspecified"))
      (node (ref "U7") (pin "39") (pinfunction "GPIO35_39") (pintype "unspecified"))
    )
    (net (code "18") (name "MOSI_S") (class "Default")
      (node (ref "CARD1") (pin "3") (pinfunction "CMD(DI)_3") (pintype "input"))
      (node (ref "R2") (pin "1") (pinfunction "1_1") (pintype "input"))
      (node (ref "U7") (pin "16") (pinfunction "GPIO11_16") (pintype "unspecified"))
    )
    (net (code "19") (name "MTCK") (class "Default")
      (node (ref "MTCK") (pin "1") (pinfunction "1_1") (pintype "unspecified"))
      (node (ref "U7") (pin "43") (pinfunction "MTCK_43") (pintype "unspecified"))
    )
    (net (code "20") (name "MTDI") (class "Default")
      (node (ref "MTDI") (pin "1") (pinfunction "1_1") (pintype "unspecified"))
      (node (ref "U7") (pin "46") (pinfunction "MTDI_46") (pintype "unspecified"))
    )
    (net (code "21") (name "MTDO") (class "Default")
      (node (ref "MTDO") (pin "1") (pinfunction "1_1") (pintype "unspecified"))
      (node (ref "U7") (pin "44") (pinfunction "MTD0_44") (pintype "unspecified"))
    )
    (net (code "22") (name "MTMS") (class "Default")
      (node (ref "MTMS") (pin "1") (pinfunction "1_1") (pintype "unspecified"))
      (node (ref "U7") (pin "47") (pinfunction "MTMS_47") (pintype "unspecified"))
    )
    (net (code "23") (name "Net-(BLINK-K)") (class "Default")
      (node (ref "BLINK") (pin "2") (pinfunction "K_2") (pintype "unspecified"))
      (node (ref "R8") (pin "2") (pinfunction "2_2") (pintype "input"))
    )
    (net (code "24") (name "Net-(C26-Pad2)") (class "Default")
      (node (ref "C26") (pin "2") (pinfunction "2_2") (pintype "unspecified"))
      (node (ref "L3") (pin "1") (pinfunction "1_1") (pintype "unspecified"))
      (node (ref "U9") (pin "2") (pinfunction "2_2") (pintype "unspecified"))
    )
    (net (code "25") (name "Net-(JP1-SIG)") (class "Default")
      (node (ref "C8") (pin "2") (pinfunction "2_2") (pintype "input"))
      (node (ref "JP1") (pin "1") (pinfunction "SIG_1") (pintype "unspecified"))
      (node (ref "L1") (pin "2") (pinfunction "2_2") (pintype "unspecified"))
    )
    (net (code "26") (name "Net-(PWR-K)") (class "Default")
      (node (ref "PWR") (pin "2") (pinfunction "K_2") (pintype "unspecified"))
      (node (ref "R7") (pin "1") (pinfunction "1_1") (pintype "input"))
    )
    (net (code "27") (name "Net-(Q1-D)") (class "Default")
      (node (ref "CN1") (pin "1") (pinfunction "1_1") (pintype "unspecified"))
      (node (ref "Q1") (pin "3") (pinfunction "D_3") (pintype "unspecified"))
    )
    (net (code "28") (name "Net-(U7-SPICLK)") (class "Default")
      (node (ref "R11") (pin "2") (pinfunction "2_2") (pintype "unspecified"))
      (node (ref "U7") (pin "34") (pinfunction "SPICLK_34") (pintype "unspecified"))
    )
    (net (code "29") (name "Net-(U8-RF_IN)") (class "Default")
      (node (ref "C27") (pin "2") (pinfunction "2_2") (pintype "input"))
      (node (ref "L3") (pin "2") (pinfunction "2_2") (pintype "unspecified"))
      (node (ref "U8") (pin "3") (pinfunction "RF_IN_3") (pintype "unspecified"))
    )
    (net (code "30") (name "Net-(X1-OSC1)") (class "Default")
      (node (ref "C25") (pin "2") (pinfunction "2_2") (pintype "unspecified"))
      (node (ref "R12") (pin "1") (pinfunction "1_1") (pintype "unspecified"))
      (node (ref "X1") (pin "1") (pinfunction "OSC1_1") (pintype "unspecified"))
    )
    (net (code "31") (name "RESET") (class "Default")
      (node (ref "C12") (pin "2") (pinfunction "2_2") (pintype "input"))
      (node (ref "R9") (pin "1") (pinfunction "1_1") (pintype "input"))
      (node (ref "RST1") (pin "1") (pinfunction "1_1") (pintype "unspecified"))
      (node (ref "U7") (pin "56") (pinfunction "CHIP_PU_56") (pintype "unspecified"))
    )
    (net (code "32") (name "RF_OUT") (class "Default")
      (node (ref "JP2") (pin "1") (pinfunction "SIG_1") (pintype "unspecified"))
      (node (ref "RF_OUT") (pin "1") (pinfunction "1_1") (pintype "unspecified"))
      (node (ref "U8") (pin "4") (pinfunction "RF_OUT_4") (pintype "unspecified"))
    )
    (net (code "33") (name "RST_A") (class "Default")
      (node (ref "U4") (pin "8") (pinfunction "RST_8") (pintype "unspecified"))
      (node (ref "U7") (pin "28") (pinfunction "GPIO21_28") (pintype "unspecified"))
    )
    (net (code "34") (name "RXEN") (class "Default")
      (node (ref "U4") (pin "17") (pinfunction "RXEN_17") (pintype "unspecified"))
      (node (ref "U7") (pin "24") (pinfunction "DAC_2_24") (pintype "unspecified"))
    )
    (net (code "35") (name "SCK_A") (class "Default")
      (node (ref "U4") (pin "12") (pinfunction "SCK_12") (pintype "unspecified"))
      (node (ref "U7") (pin "40") (pinfunction "GPIO36_40") (pintype "unspecified"))
    )
    (net (code "36") (name "SCK_S") (class "Default")
      (node (ref "CARD1") (pin "5") (pinfunction "CLK(SCLK)_5") (pintype "input"))
      (node (ref "R3") (pin "1") (pinfunction "1_1") (pintype "input"))
      (node (ref "U7") (pin "17") (pinfunction "GPIO12_17") (pintype "unspecified"))
    )
    (net (code "37") (name "SCL_A") (class "Default")
      (node (ref "H2") (pin "2") (pinfunction "2_2") (pintype "unspecified"))
      (node (ref "U7") (pin "13") (pinfunction "GPIO8_13") (pintype "unspecified"))
    )
    (net (code "38") (name "SCL_FC") (class "Default")
      (node (ref "H1") (pin "3") (pinfunction "3_3") (pintype "unspecified"))
      (node (ref "U7") (pin "11") (pinfunction "GPIO6_11") (pintype "unspecified"))
    )
    (net (code "39") (name "SDA_A") (class "Default")
      (node (ref "H2") (pin "3") (pinfunction "3_3") (pintype "unspecified"))
      (node (ref "U7") (pin "12") (pinfunction "GPIO7_12") (pintype "unspecified"))
    )
    (net (code "40") (name "SDA_FC") (class "Default")
      (node (ref "H1") (pin "2") (pinfunction "2_2") (pintype "unspecified"))
      (node (ref "U7") (pin "10") (pinfunction "GPIO5_10") (pintype "unspecified"))
    )
    (net (code "41") (name "SPICLK") (class "Default")
      (node (ref "R11") (pin "1") (pinfunction "1_1") (pintype "unspecified"))
      (node (ref "U5") (pin "6") (pinfunction "CLK_6") (pintype "unspecified"))
      (node (ref "U6") (pin "6") (pinfunction "SCLK_6") (pintype "unspecified"))
    )
    (net (code "42") (name "SPICS0") (class "Default")
      (node (ref "R5") (pin "1") (pinfunction "1_1") (pintype "input"))
      (node (ref "U5") (pin "1") (pinfunction "CS#_1") (pintype "unspecified"))
      (node (ref "U7") (pin "33") (pinfunction "SPICS0_33") (pintype "unspecified"))
    )
    (net (code "43") (name "SPICS1") (class "Default")
      (node (ref "R6") (pin "1") (pinfunction "1_1") (pintype "input"))
      (node (ref "U6") (pin "1") (pinfunction "CE#_1") (pintype "unspecified"))
      (node (ref "U7") (pin "29") (pinfunction "SPICS1_29") (pintype "unspecified"))
    )
    (net (code "44") (name "SPID") (class "Default")
      (node (ref "U5") (pin "5") (pinfunction "DI（IO0）_5") (pintype "unspecified"))
      (node (ref "U6") (pin "5") (pinfunction "SI/SIO[0]_5") (pintype "unspecified"))
      (node (ref "U7") (pin "36") (pinfunction "SPID_36") (pintype "unspecified"))
    )
    (net (code "45") (name "SPIHD") (class "Default")
      (node (ref "U5") (pin "7") (pinfunction "IO3_7") (pintype "unspecified"))
      (node (ref "U6") (pin "7") (pinfunction "SIO[3]_7") (pintype "unspecified"))
      (node (ref "U7") (pin "31") (pinfunction "SPIHD_31") (pintype "unspecified"))
    )
    (net (code "46") (name "SPIQ") (class "Default")
      (node (ref "U5") (pin "2") (pinfunction "DO（IO1）_2") (pintype "unspecified"))
      (node (ref "U6") (pin "2") (pinfunction "SO/SIO[1]_2") (pintype "unspecified"))
      (node (ref "U7") (pin "35") (pinfunction "SPIQ_35") (pintype "unspecified"))
    )
    (net (code "47") (name "SPIWP") (class "Default")
      (node (ref "U5") (pin "3") (pinfunction "IO2_3") (pintype "unspecified"))
      (node (ref "U6") (pin "3") (pinfunction "SIO[2]_3") (pintype "unspecified"))
      (node (ref "U7") (pin "32") (pinfunction "SPIWP_32") (pintype "unspecified"))
    )
    (net (code "48") (name "STATUSLED") (class "Default")
      (node (ref "STATUS") (pin "4") (pinfunction "DIN_4") (pintype "unspecified"))
      (node (ref "U7") (pin "7") (pinfunction "GPIO2_7") (pintype "unspecified"))
    )
    (net (code "49") (name "TXEN") (class "Default")
      (node (ref "U4") (pin "16") (pinfunction "TXEN_16") (pintype "unspecified"))
      (node (ref "U7") (pin "23") (pinfunction "DAC_1_23") (pintype "unspecified"))
    )
    (net (code "50") (name "U0RXD") (class "Default")
      (node (ref "H3") (pin "2") (pinfunction "2_2") (pintype "unspecified"))
      (node (ref "U7") (pin "49") (pinfunction "U0RXD_49") (pintype "unspecified"))
    )
    (net (code "51") (name "U0TXD") (class "Default")
      (node (ref "H3") (pin "3") (pinfunction "3_3") (pintype "unspecified"))
      (node (ref "U7") (pin "48") (pinfunction "U0TXD_48") (pintype "unspecified"))
    )
    (net (code "52") (name "USB_D+") (class "Default")
      (node (ref "U7") (pin "26") (pinfunction "GPIO20_26") (pintype "unspecified"))
      (node (ref "USB1") (pin "3") (pinfunction "D+_3") (pintype "unspecified"))
    )
    (net (code "53") (name "USB_D-") (class "Default")
      (node (ref "U7") (pin "25") (pinfunction "GPIO19_25") (pintype "unspecified"))
      (node (ref "USB1") (pin "2") (pinfunction "D-_2") (pintype "unspecified"))
    )
    (net (code "54") (name "VDD3P3") (class "Default")
      (node (ref "C21") (pin "2") (pinfunction "2_2") (pintype "input"))
      (node (ref "L2") (pin "2") (pinfunction "2_2") (pintype "unspecified"))
      (node (ref "U7") (pin "3") (pinfunction "VDD3P3_3") (pintype "unspecified"))
      (node (ref "U7") (pin "4") (pinfunction "VDD3P3_4") (pintype "unspecified"))
    )
    (net (code "55") (name "VDD_SPI") (class "Default")
      (node (ref "C10") (pin "2") (pinfunction "2_2") (pintype "input"))
      (node (ref "C19") (pin "2") (pinfunction "2_2") (pintype "input"))
      (node (ref "C9") (pin "2") (pinfunction "2_2") (pintype "input"))
      (node (ref "R5") (pin "2") (pinfunction "2_2") (pintype "input"))
      (node (ref "R6") (pin "2") (pinfunction "2_2") (pintype "input"))
      (node (ref "U5") (pin "8") (pinfunction "VCC_8") (pintype "unspecified"))
      (node (ref "U6") (pin "8") (pinfunction "VCC_8") (pintype "unspecified"))
      (node (ref "U7") (pin "30") (pinfunction "VDD_SPI_30") (pintype "unspecified"))
    )
    (net (code "56") (name "XTAL_N") (class "Default")
      (node (ref "C24") (pin "2") (pinfunction "2_2") (pintype "unspecified"))
      (node (ref "U7") (pin "52") (pinfunction "XTAL_N_52") (pintype "unspecified"))
      (node (ref "X1") (pin "3") (pinfunction "OSC2_3") (pintype "unspecified"))
    )
    (net (code "57") (name "XTAL_P") (class "Default")
      (node (ref "R12") (pin "2") (pinfunction "2_2") (pintype "unspecified"))
      (node (ref "U7") (pin "53") (pinfunction "XTAL_P_53") (pintype "unspecified"))
    )
    (net (code "58") (name "unconnected-(CARD1-CD-Pad9)") (class "Default")
      (node (ref "CARD1") (pin "9") (pinfunction "CD_9") (pintype "input+no_connect"))
    )
    (net (code "59") (name "unconnected-(CARD1-DAT1(RSV)-Pad8)") (class "Default")
      (node (ref "CARD1") (pin "8") (pinfunction "DAT1(RSV)_8") (pintype "bidirectional+no_connect"))
    )
    (net (code "60") (name "unconnected-(CARD1-DAT2(RSV)-Pad1)") (class "Default")
      (node (ref "CARD1") (pin "1") (pinfunction "DAT2(RSV)_1") (pintype "bidirectional+no_connect"))
    )
    (net (code "61") (name "unconnected-(STATUS-DOUT-Pad2)") (class "Default")
      (node (ref "STATUS") (pin "2") (pinfunction "DOUT_2") (pintype "unspecified+no_connect"))
    )
    (net (code "62") (name "unconnected-(U4-DIO2-Pad5)") (class "Default")
      (node (ref "U4") (pin "5") (pinfunction "DIO2_5") (pintype "unspecified+no_connect"))
    )
    (net (code "63") (name "unconnected-(U4-DIO3-Pad4)") (class "Default")
      (node (ref "U4") (pin "4") (pinfunction "DIO3_4") (pintype "unspecified+no_connect"))
    )
    (net (code "64") (name "unconnected-(U4-DIO4-Pad3)") (class "Default")
      (node (ref "U4") (pin "3") (pinfunction "DIO4_3") (pintype "unspecified+no_connect"))
    )
    (net (code "65") (name "unconnected-(U4-DIO5-Pad2)") (class "Default")
      (node (ref "U4") (pin "2") (pinfunction "DIO5_2") (pintype "unspecified+no_connect"))
    )
    (net (code "66") (name "unconnected-(U4-NC-Pad9)") (class "Default")
      (node (ref "U4") (pin "9") (pinfunction "NC_9") (pintype "unspecified+no_connect"))
    )
    (net (code "67") (name "unconnected-(U7-GPIO9-Pad14)") (class "Default")
      (node (ref "U7") (pin "14") (pinfunction "GPIO9_14") (pintype "unspecified+no_connect"))
    )
    (net (code "68") (name "unconnected-(U7-GPIO14-Pad19)") (class "Default")
      (node (ref "U7") (pin "19") (pinfunction "GPIO14_19") (pintype "unspecified+no_connect"))
    )
    (net (code "69") (name "unconnected-(U7-GPIO33-Pad37)") (class "Default")
      (node (ref "U7") (pin "37") (pinfunction "GPIO33_37") (pintype "unspecified+no_connect"))
    )
    (net (code "70") (name "unconnected-(U7-GPIO38-Pad42)") (class "Default")
      (node (ref "U7") (pin "42") (pinfunction "GPIO38_42") (pintype "unspecified+no_connect"))
    )
    (net (code "71") (name "unconnected-(U8-EP-Pad7)") (class "Default")
      (node (ref "U8") (pin "7") (pinfunction "EP_7") (pintype "unspecified+no_connect"))
    )
    (net (code "72") (name "unconnected-(USB1-ID-Pad4)") (class "Default")
      (node (ref "USB1") (pin "4") (pinfunction "ID_4") (pintype "unspecified+no_connect"))
    )
  )
)
